# Flight-Mill-Controller.net
KiCad netlist of a schematic drawn in EAGLE
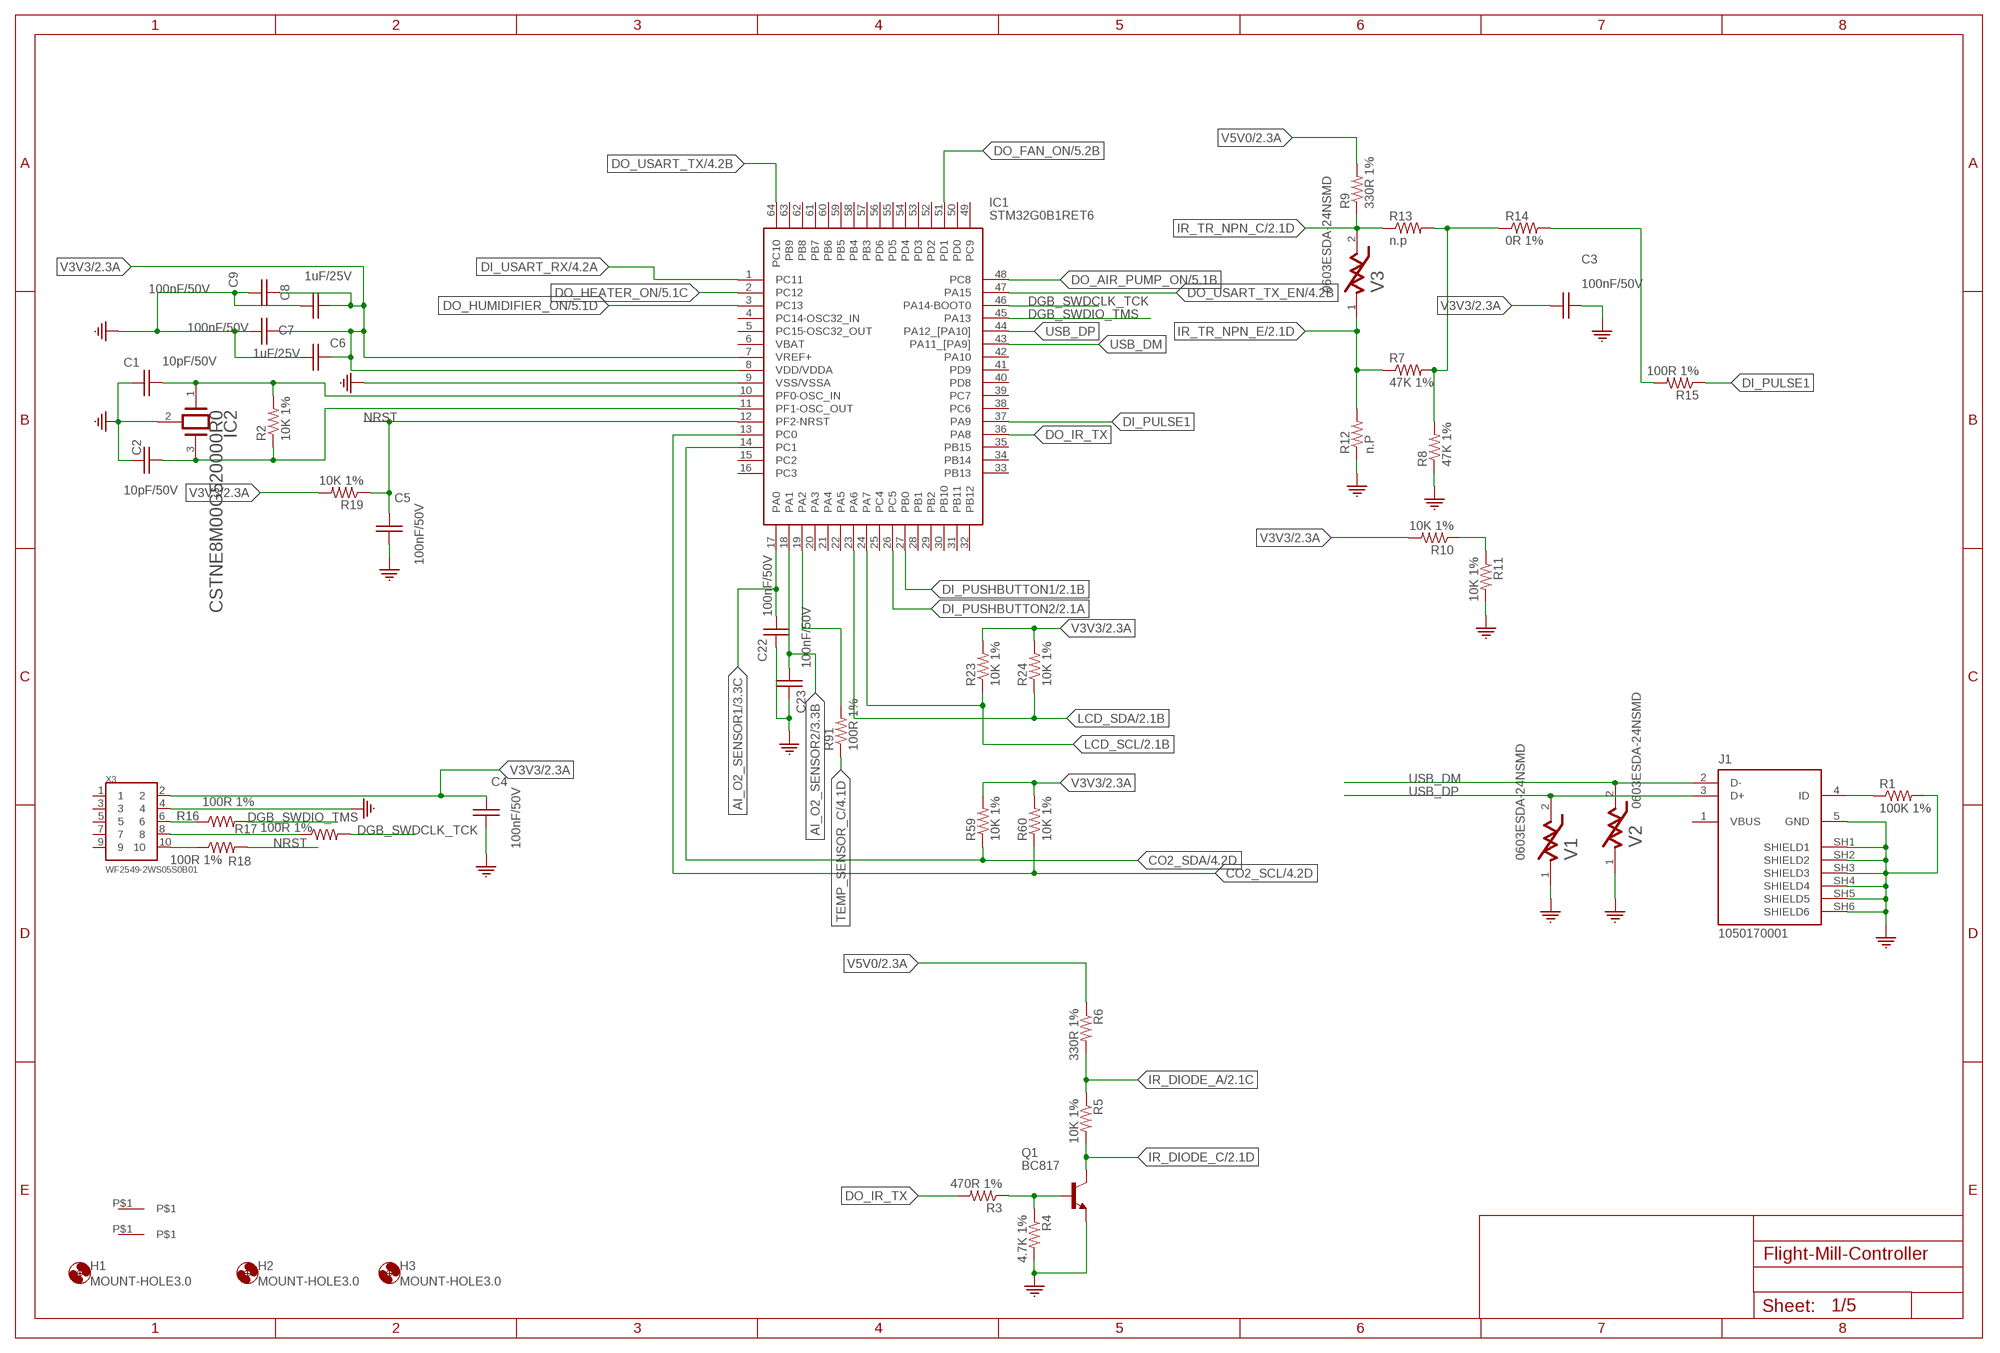
[diagram p0: schematic, sheet 1]
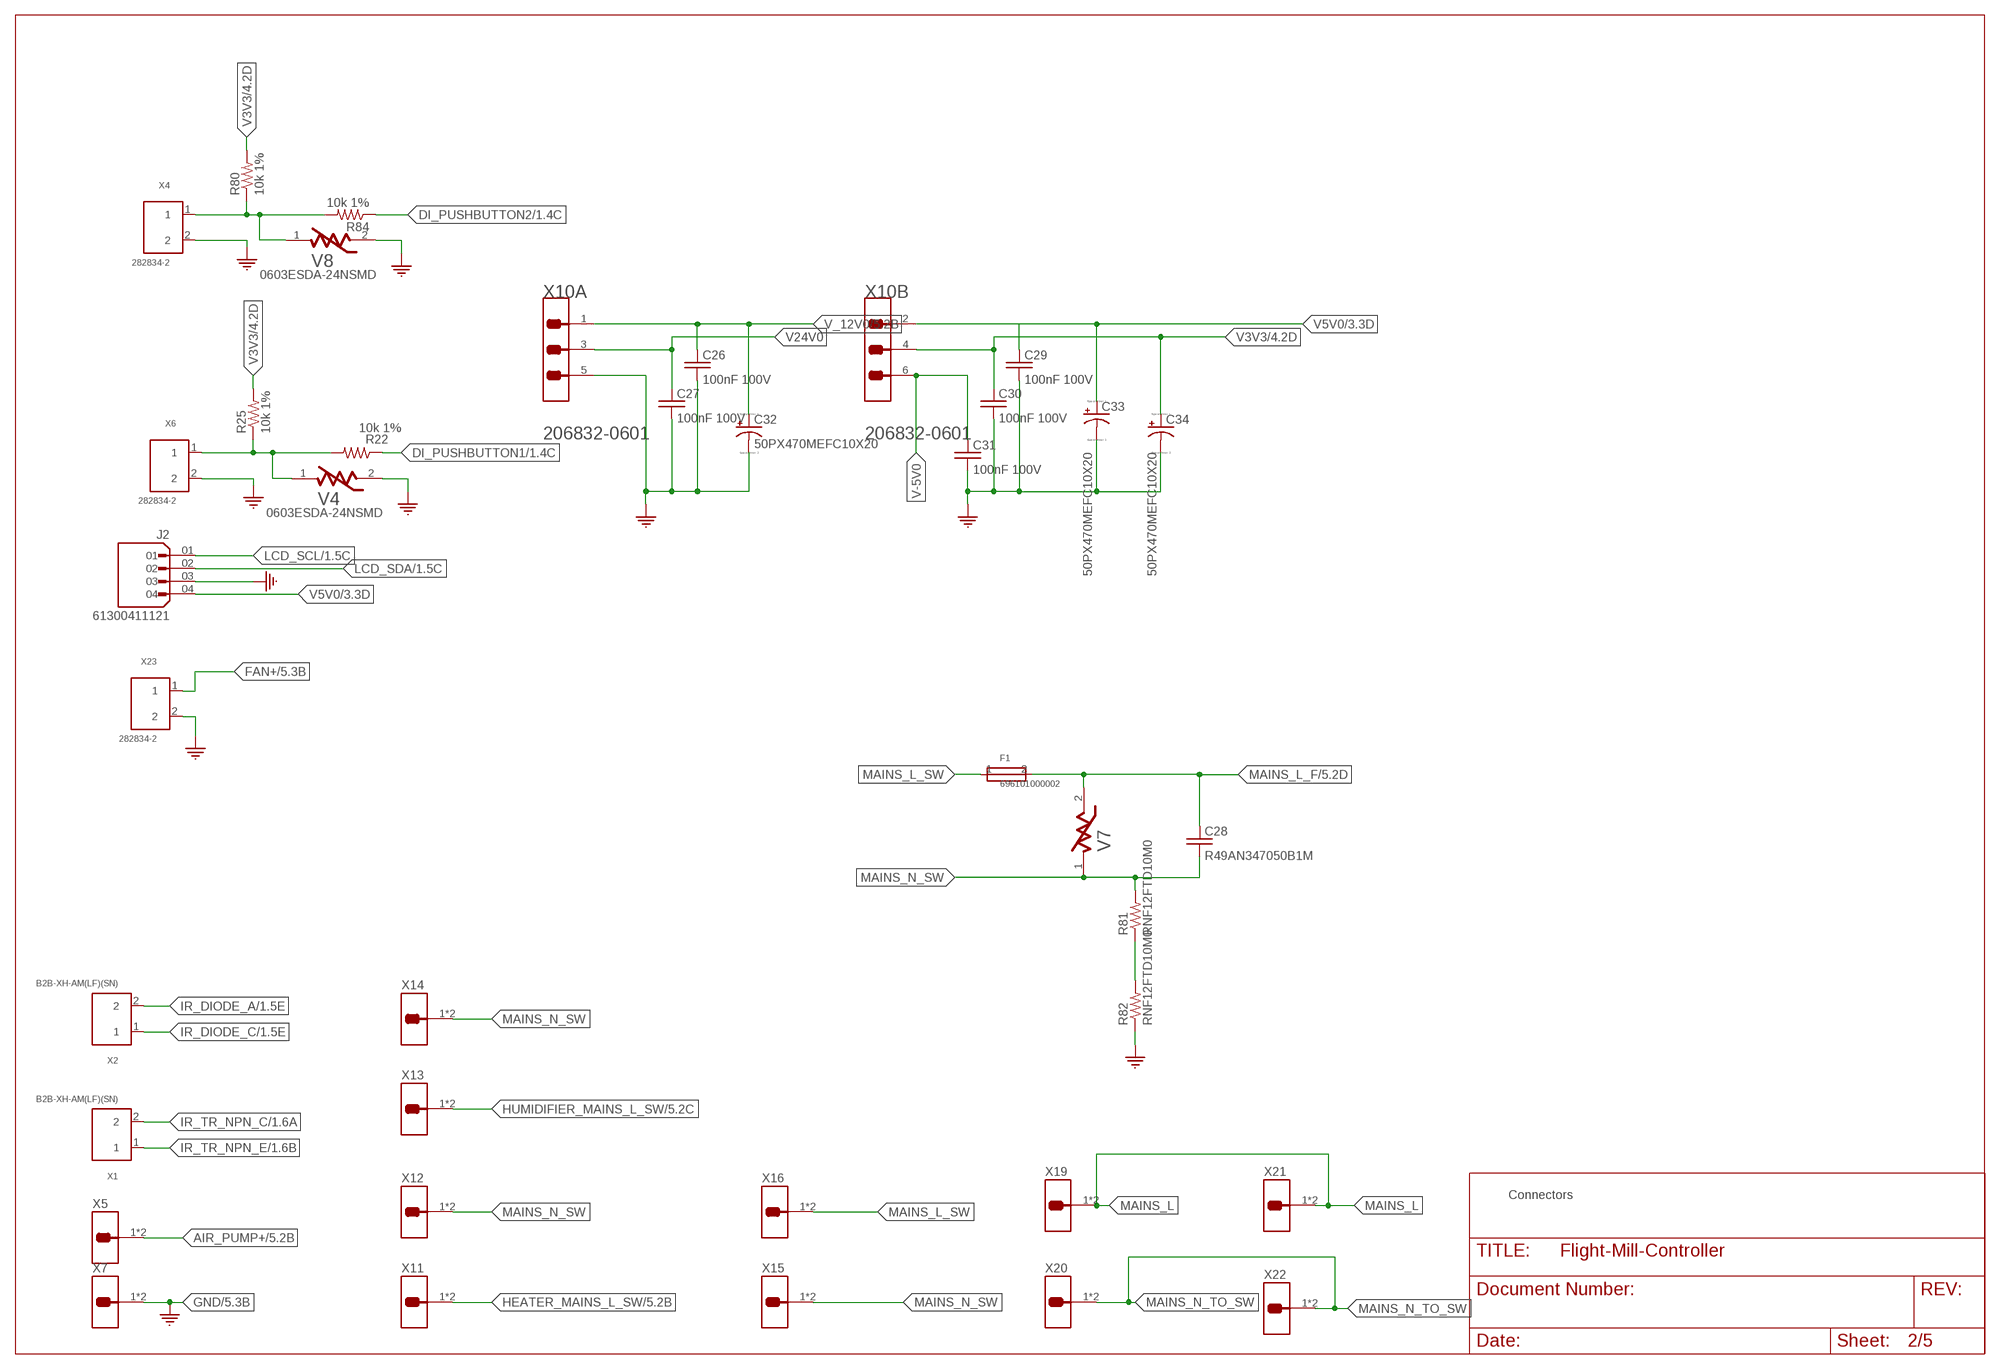
[diagram p1: schematic, sheet 2]
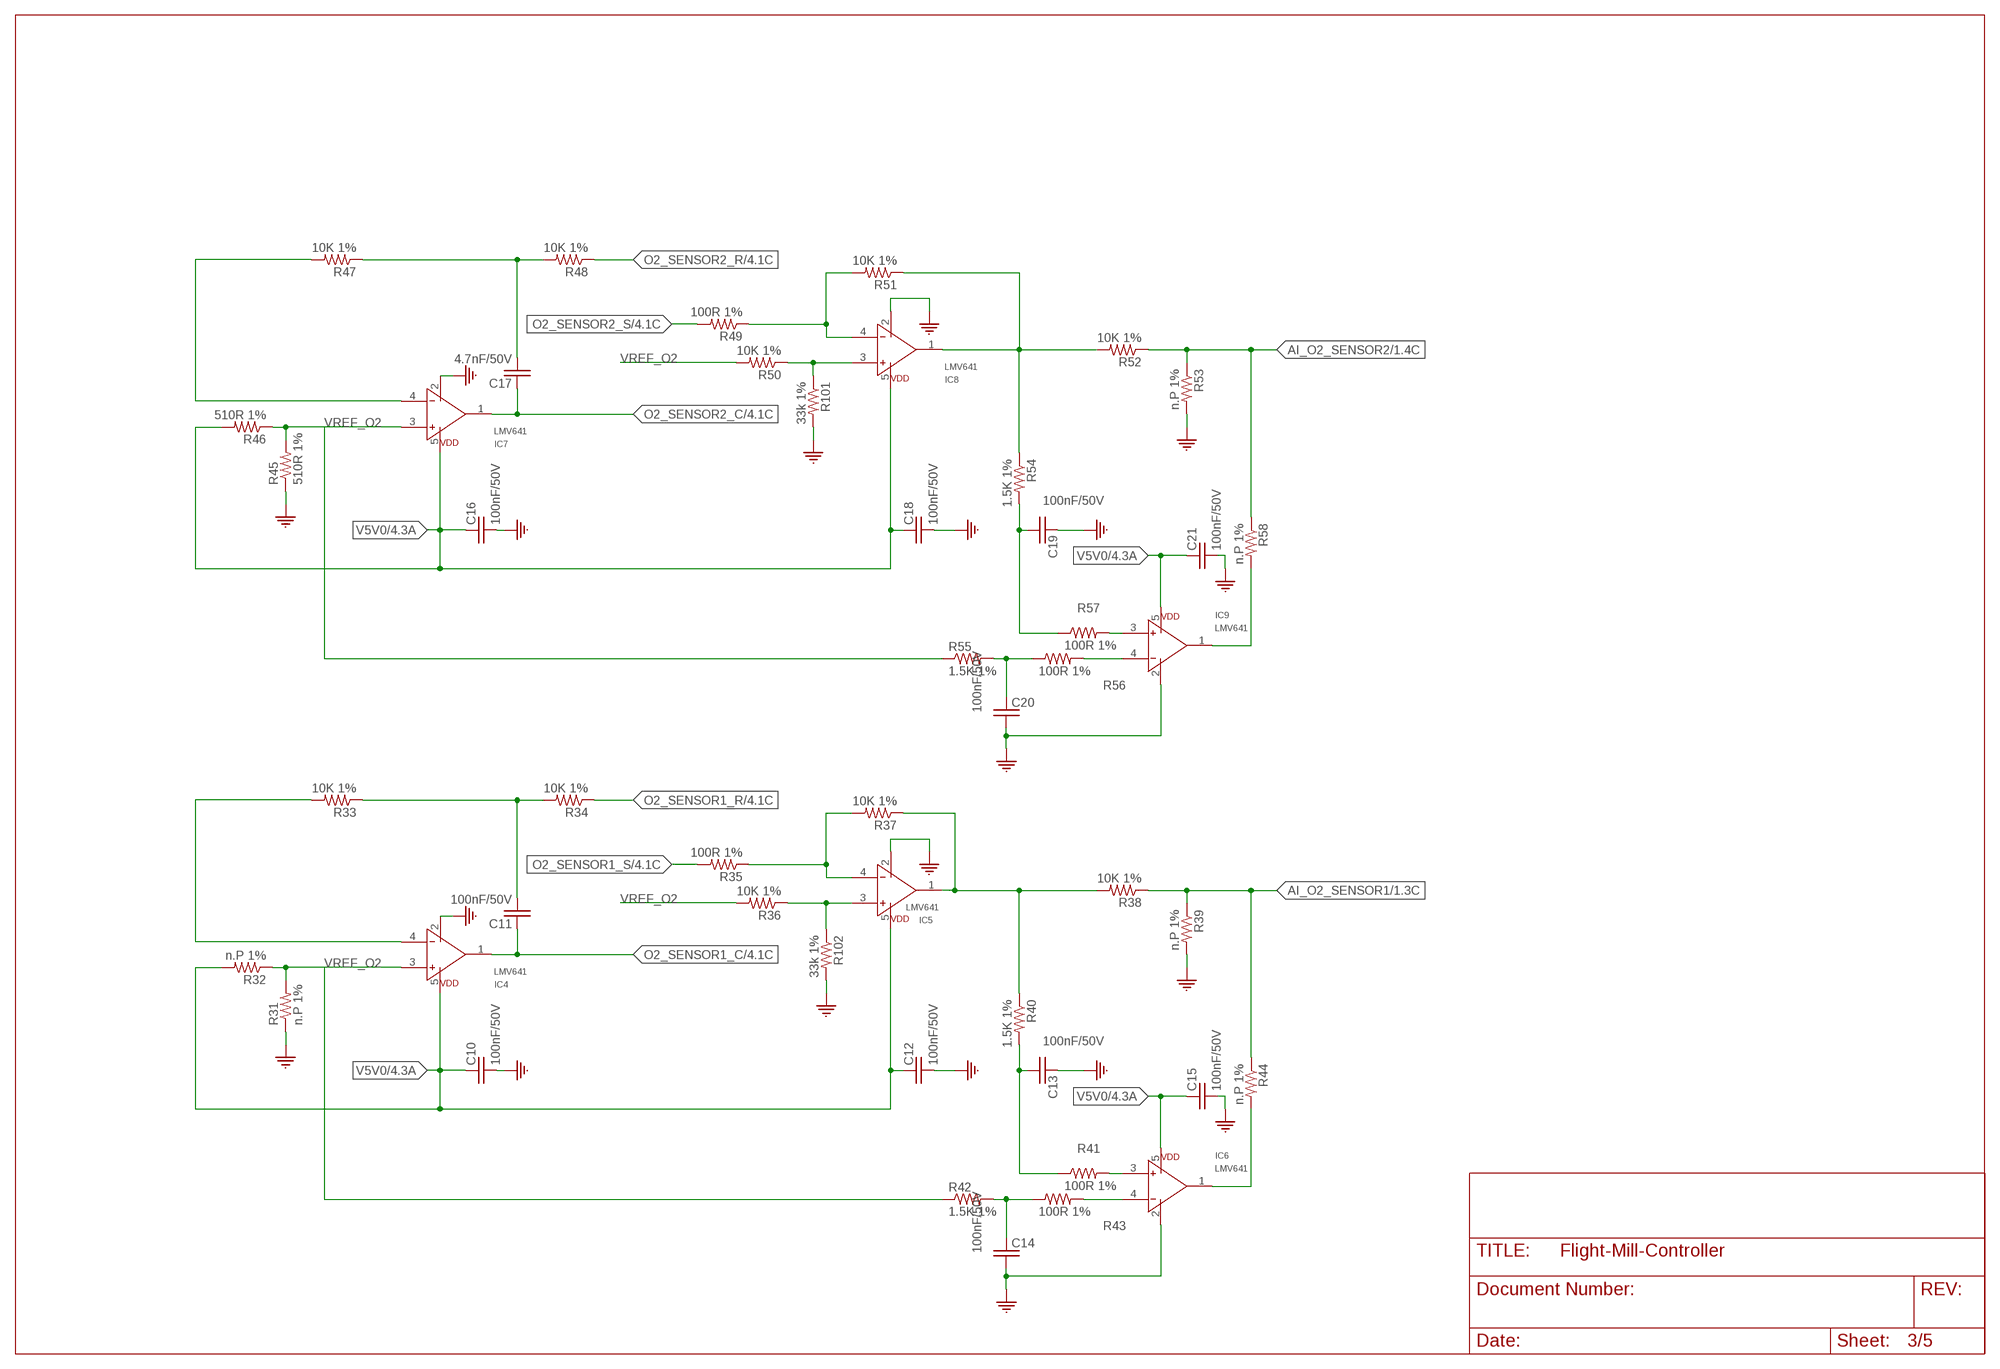
[diagram p2: schematic, sheet 3]
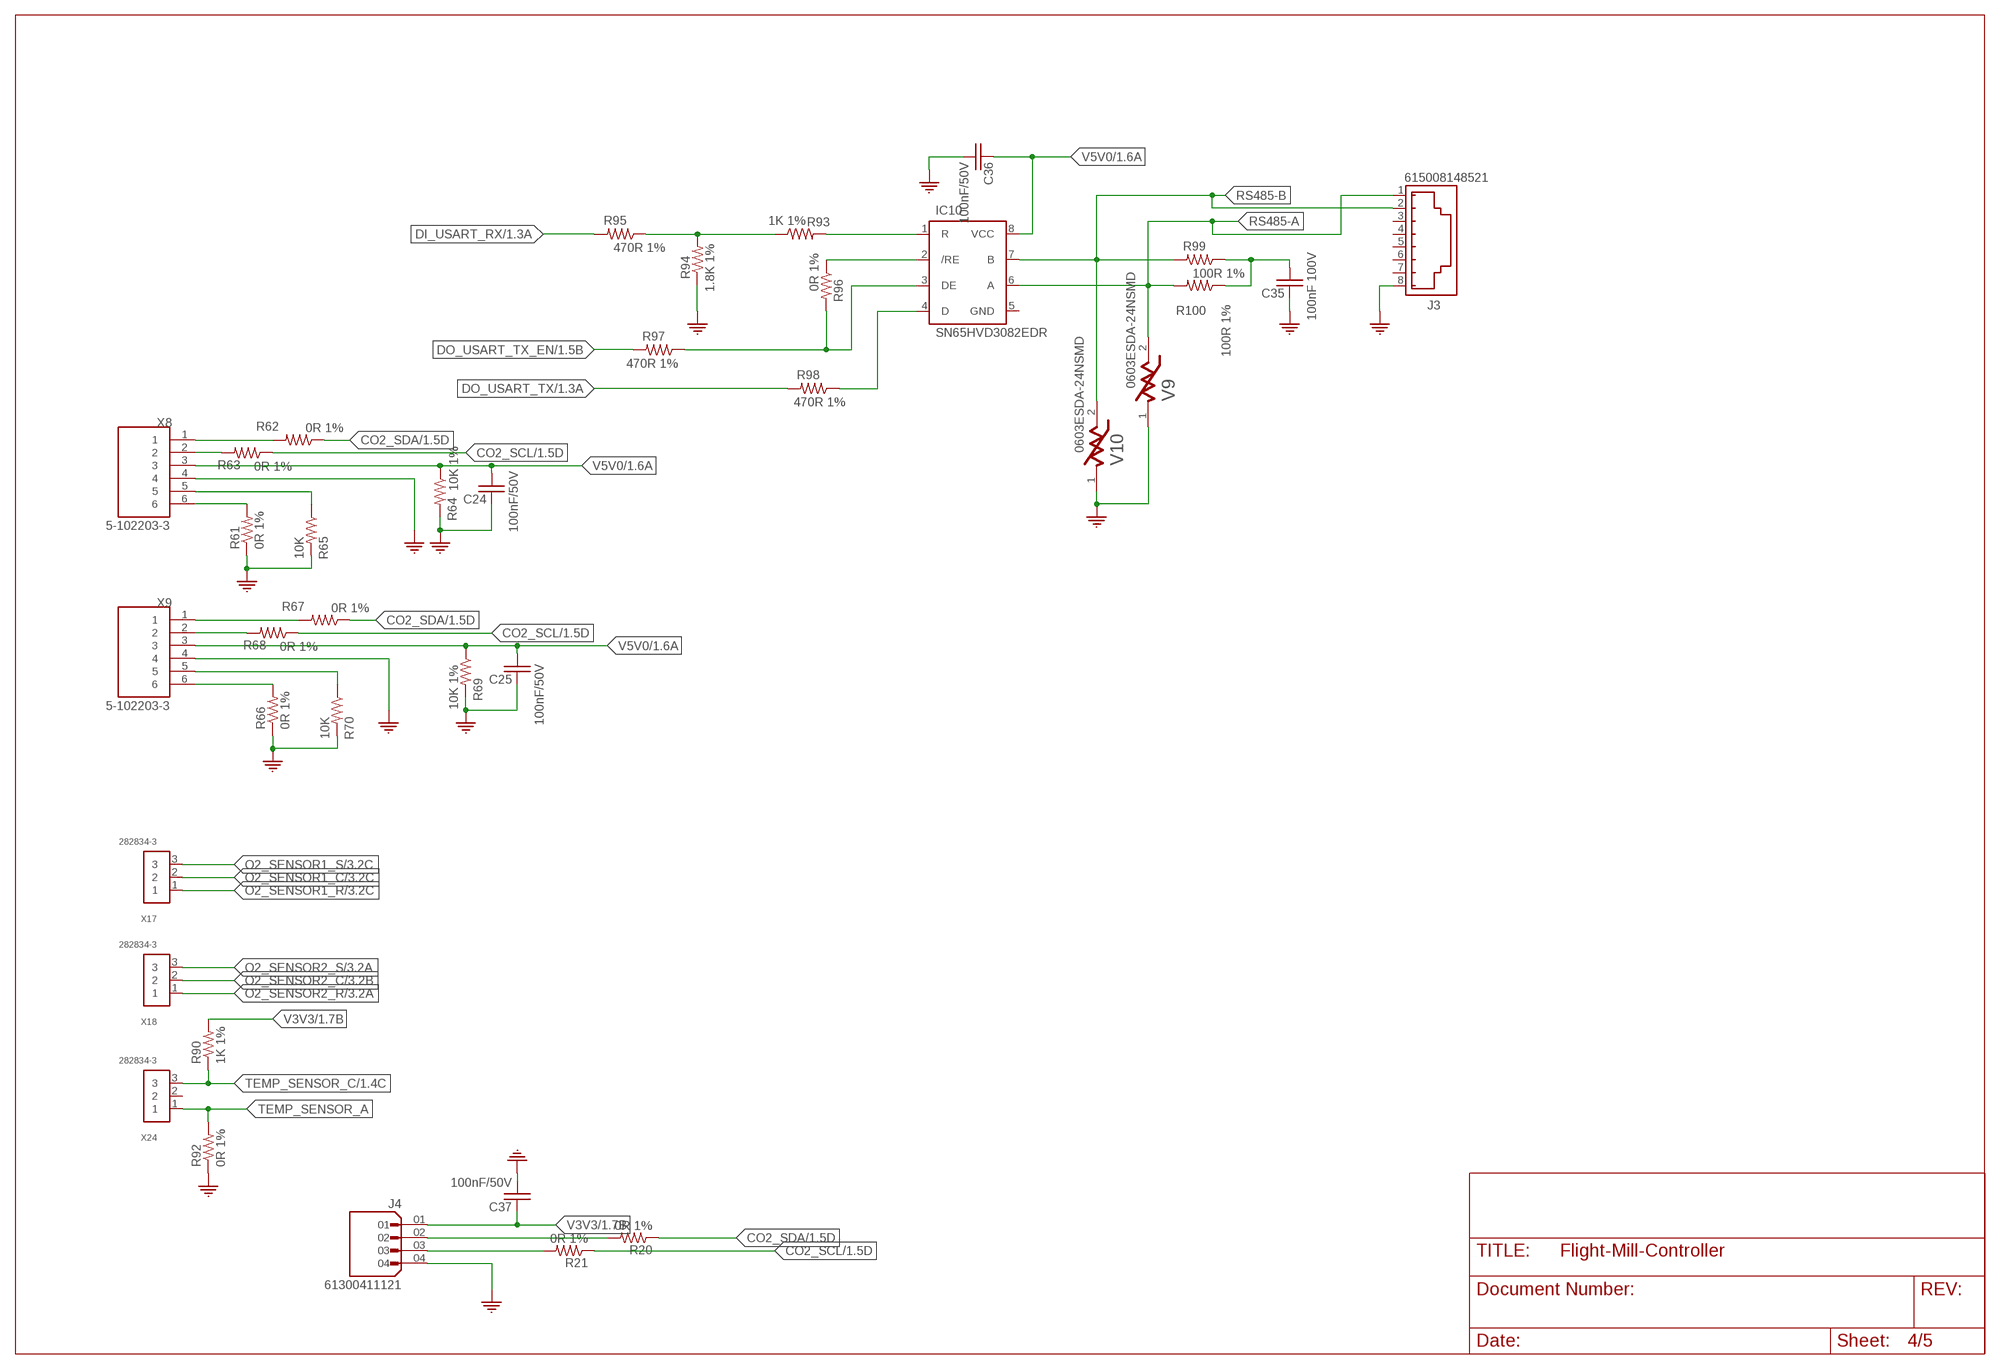
[diagram p3: schematic, sheet 4]
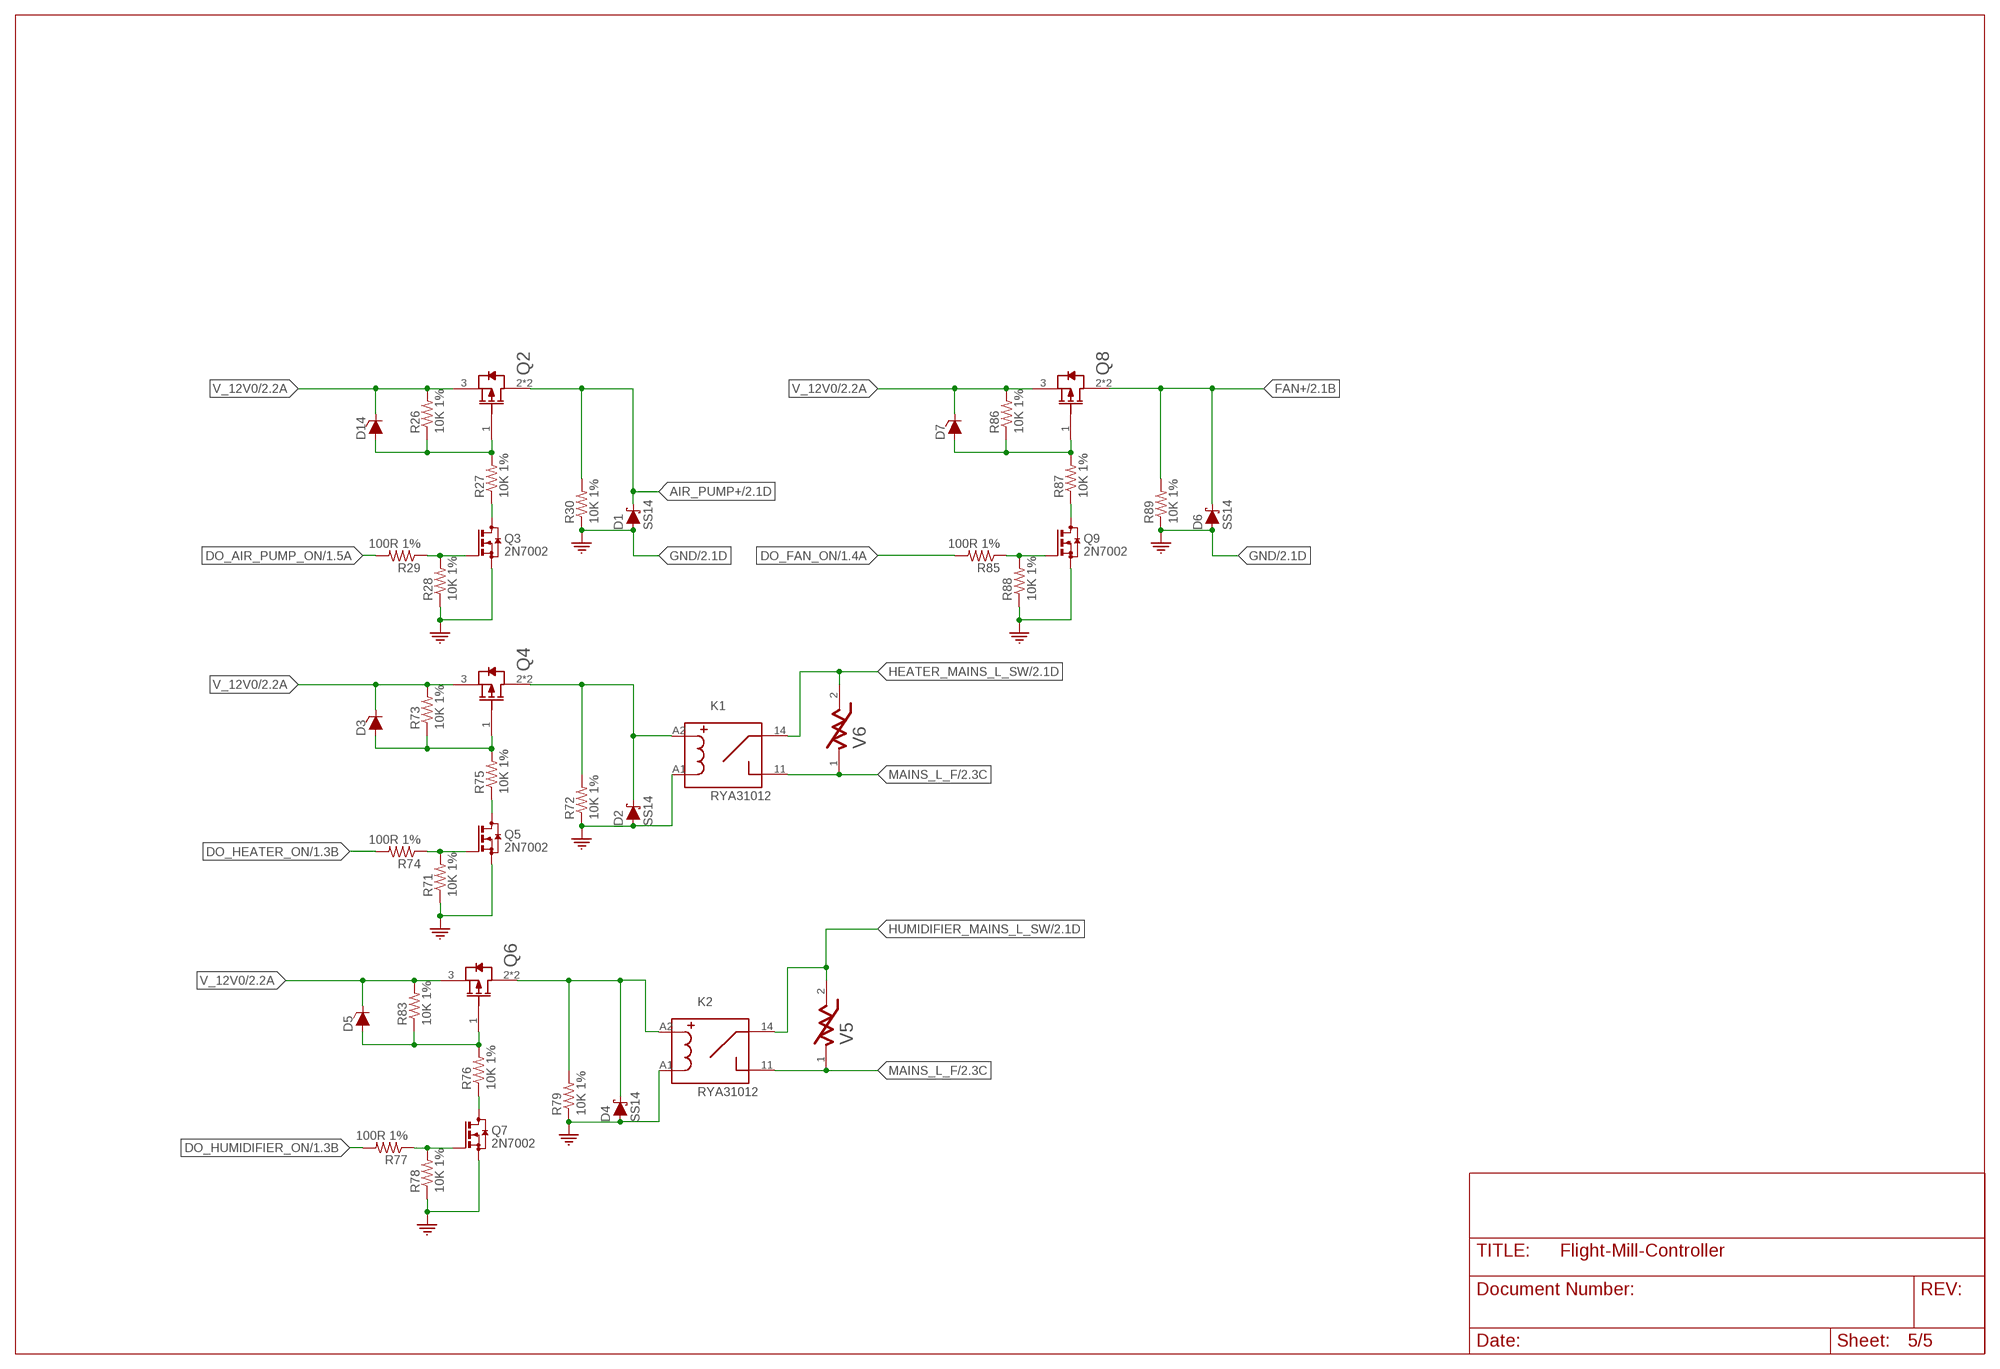
[diagram p4: schematic, sheet 5]

(export (version "E")
  (design (tool "Eeschema 10.0.6"))
  (components
    (comp (ref "C1")
      (value "10pF/50V")
      (footprint "eagle-import:EIA0603")
      (libsource (lib "eagle-import") (part "C_0603EIA0603"))
    )
    (comp (ref "C2")
      (value "10pF/50V")
      (footprint "eagle-import:EIA0603")
      (libsource (lib "eagle-import") (part "C_0603EIA0603"))
    )
    (comp (ref "C3")
      (value "100nF/50V")
      (footprint "eagle-import:EIA0603")
      (libsource (lib "eagle-import") (part "C_0603EIA0603"))
    )
    (comp (ref "C4")
      (value "100nF/50V")
      (footprint "eagle-import:EIA0603")
      (libsource (lib "eagle-import") (part "C_0603EIA0603"))
    )
    (comp (ref "C5")
      (value "100nF/50V")
      (footprint "eagle-import:EIA0603")
      (libsource (lib "eagle-import") (part "C_0603EIA0603"))
    )
    (comp (ref "C6")
      (value "1uF/25V")
      (footprint "eagle-import:EIA0603")
      (libsource (lib "eagle-import") (part "C_0603EIA0603"))
    )
    (comp (ref "C7")
      (value "100nF/50V")
      (footprint "eagle-import:EIA0603")
      (libsource (lib "eagle-import") (part "C_0603EIA0603"))
    )
    (comp (ref "C8")
      (value "1uF/25V")
      (footprint "eagle-import:EIA0603")
      (libsource (lib "eagle-import") (part "C_0603EIA0603"))
    )
    (comp (ref "C9")
      (value "100nF/50V")
      (footprint "eagle-import:EIA0603")
      (libsource (lib "eagle-import") (part "C_0603EIA0603"))
    )
    (comp (ref "C22")
      (value "100nF/50V")
      (footprint "eagle-import:EIA0603")
      (libsource (lib "eagle-import") (part "C_0603EIA0603"))
    )
    (comp (ref "C23")
      (value "100nF/50V")
      (footprint "eagle-import:EIA0603")
      (libsource (lib "eagle-import") (part "C_0603EIA0603"))
    )
    (comp (ref "FID1")
      (value "FIDUCIAL")
      (footprint "eagle-import:FIDUCIAL")
      (libsource (lib "eagle-import") (part "FIDUCIAL"))
    )
    (comp (ref "FID2")
      (value "FIDUCIAL")
      (footprint "eagle-import:FIDUCIAL")
      (libsource (lib "eagle-import") (part "FIDUCIAL"))
    )
    (comp (ref "H1")
      (value "MOUNT-HOLE3.0")
      (footprint "eagle-import:3,0")
      (libsource (lib "eagle-import") (part "MOUNT-HOLE3.0"))
    )
    (comp (ref "H2")
      (value "MOUNT-HOLE3.0")
      (footprint "eagle-import:3,0")
      (libsource (lib "eagle-import") (part "MOUNT-HOLE3.0"))
    )
    (comp (ref "H3")
      (value "MOUNT-HOLE3.0")
      (footprint "eagle-import:3,0")
      (libsource (lib "eagle-import") (part "MOUNT-HOLE3.0"))
    )
    (comp (ref "IC1")
      (value "STM32G0B1RET6")
      (footprint "eagle-import:QFP50P1200X1200X160-64N")
      (fields (field (name "MOUSER_PART_NUMBER") "511-STM32G0B1RET6"))
      (libsource (lib "eagle-import") (part "STM32G0B1RET6"))
    )
    (comp (ref "IC2")
      (value "CSTNE8M00G520000R0")
      (footprint "eagle-import:CSTNE8M00G520000R0")
      (fields (field (name "MFR") "Murata"))
      (libsource (lib "eagle-import") (part "CSTNE8M00G520000R0"))
    )
    (comp (ref "J1")
      (value "1050170001")
      (footprint "eagle-import:MOLEX_1050170001")
      (fields (field (name "MF") "Molex"))
      (libsource (lib "eagle-import") (part "1050170001"))
    )
    (comp (ref "Q1")
      (value "BC817")
      (footprint "eagle-import:SOT23")
      (fields (field (name "MFR") "NXP"))
      (libsource (lib "eagle-import") (part "BC817"))
    )
    (comp (ref "R1")
      (value "100K 1%")
      (footprint "eagle-import:EIA0603")
      (libsource (lib "eagle-import") (part "R_0603"))
    )
    (comp (ref "R2")
      (value "10K 1%")
      (footprint "eagle-import:EIA0603")
      (libsource (lib "eagle-import") (part "R_0603"))
    )
    (comp (ref "R3")
      (value "470R 1%")
      (footprint "eagle-import:EIA0603")
      (libsource (lib "eagle-import") (part "R_0603"))
    )
    (comp (ref "R4")
      (value "4.7K 1%")
      (footprint "eagle-import:EIA0603")
      (libsource (lib "eagle-import") (part "R_0603"))
    )
    (comp (ref "R5")
      (value "10K 1%")
      (footprint "eagle-import:EIA0603")
      (libsource (lib "eagle-import") (part "R_0603"))
    )
    (comp (ref "R6")
      (value "330R 1%")
      (footprint "eagle-import:EIA0603")
      (libsource (lib "eagle-import") (part "R_0603"))
    )
    (comp (ref "R7")
      (value "47K 1%")
      (footprint "eagle-import:EIA0603")
      (libsource (lib "eagle-import") (part "R_0603"))
    )
    (comp (ref "R8")
      (value "47K 1%")
      (footprint "eagle-import:EIA0603")
      (libsource (lib "eagle-import") (part "R_0603"))
    )
    (comp (ref "R9")
      (value "330R 1%")
      (footprint "eagle-import:EIA0603")
      (libsource (lib "eagle-import") (part "R_0603"))
    )
    (comp (ref "R10")
      (value "10K 1%")
      (footprint "eagle-import:EIA0603")
      (libsource (lib "eagle-import") (part "R_0603"))
    )
    (comp (ref "R11")
      (value "10K 1%")
      (footprint "eagle-import:EIA0603")
      (libsource (lib "eagle-import") (part "R_0603"))
    )
    (comp (ref "R12")
      (value "n.P")
      (footprint "eagle-import:EIA0603")
      (libsource (lib "eagle-import") (part "R_0603"))
    )
    (comp (ref "R13")
      (value "n.p")
      (footprint "eagle-import:EIA0603")
      (libsource (lib "eagle-import") (part "R_0603"))
    )
    (comp (ref "R14")
      (value "0R 1%")
      (footprint "eagle-import:EIA0603")
      (libsource (lib "eagle-import") (part "R_0603"))
    )
    (comp (ref "R15")
      (value "100R 1%")
      (footprint "eagle-import:EIA0603")
      (libsource (lib "eagle-import") (part "R_0603"))
    )
    (comp (ref "R16")
      (value "100R 1%")
      (footprint "eagle-import:EIA0603")
      (libsource (lib "eagle-import") (part "R_0603"))
    )
    (comp (ref "R17")
      (value "100R 1%")
      (footprint "eagle-import:EIA0603")
      (libsource (lib "eagle-import") (part "R_0603"))
    )
    (comp (ref "R18")
      (value "100R 1%")
      (footprint "eagle-import:EIA0603")
      (libsource (lib "eagle-import") (part "R_0603"))
    )
    (comp (ref "R19")
      (value "10K 1%")
      (footprint "eagle-import:EIA0603")
      (libsource (lib "eagle-import") (part "R_0603"))
    )
    (comp (ref "R23")
      (value "10K 1%")
      (footprint "eagle-import:EIA0603")
      (libsource (lib "eagle-import") (part "R_0603"))
    )
    (comp (ref "R24")
      (value "10K 1%")
      (footprint "eagle-import:EIA0603")
      (libsource (lib "eagle-import") (part "R_0603"))
    )
    (comp (ref "R59")
      (value "10K 1%")
      (footprint "eagle-import:EIA0603")
      (libsource (lib "eagle-import") (part "R_0603"))
    )
    (comp (ref "R60")
      (value "10K 1%")
      (footprint "eagle-import:EIA0603")
      (libsource (lib "eagle-import") (part "R_0603"))
    )
    (comp (ref "R91")
      (value "100R 1%")
      (footprint "eagle-import:EIA0603")
      (libsource (lib "eagle-import") (part "R_0603"))
    )
    (comp (ref "V1")
      (value "0603ESDA-24NSMD")
      (footprint "eagle-import:EIA0603")
      (fields (field (name "MFR") "Bourns"))
      (libsource (lib "eagle-import") (part "0603ESDA-24NSMD"))
    )
    (comp (ref "V2")
      (value "0603ESDA-24NSMD")
      (footprint "eagle-import:EIA0603")
      (fields (field (name "MFR") "Bourns"))
      (libsource (lib "eagle-import") (part "0603ESDA-24NSMD"))
    )
    (comp (ref "V3")
      (value "0603ESDA-24NSMD")
      (footprint "eagle-import:EIA0603")
      (fields (field (name "MFR") "Bourns"))
      (libsource (lib "eagle-import") (part "0603ESDA-24NSMD"))
    )
    (comp (ref "X3")
      (value "WF2549-2WS05S0B01")
      (footprint "eagle-import:X10_100MIL_2XROW_VERT")
      (fields (field (name "MFR") "WCON"))
      (libsource (lib "eagle-import") (part "WF2549-2WS05S0B01"))
    )
    (comp (ref "C24")
      (value "100nF/50V")
      (footprint "eagle-import:EIA0603")
      (libsource (lib "eagle-import") (part "C_0603EIA0603"))
    )
    (comp (ref "C25")
      (value "100nF/50V")
      (footprint "eagle-import:EIA0603")
      (libsource (lib "eagle-import") (part "C_0603EIA0603"))
    )
    (comp (ref "C35")
      (value "100nF 100V")
      (footprint "eagle-import:EIA0603")
      (libsource (lib "eagle-import") (part "C_0603EIA0603"))
    )
    (comp (ref "C36")
      (value "100nF/50V")
      (footprint "eagle-import:EIA0603")
      (libsource (lib "eagle-import") (part "C_0603EIA0603"))
    )
    (comp (ref "C37")
      (value "100nF/50V")
      (footprint "eagle-import:EIA0603")
      (libsource (lib "eagle-import") (part "C_0603EIA0603"))
    )
    (comp (ref "IC10")
      (value "SN65HVD3082EDR")
      (footprint "eagle-import:SOIC8")
      (fields (field (name "MFR") "TI,3Peak"))
      (libsource (lib "eagle-import") (part "SN65HVD3082EDR"))
    )
    (comp (ref "J3")
      (value "615008148521")
      (footprint "eagle-import:615008148521")
      (fields (field (name "MFR") "Wurth Elektronik"))
      (libsource (lib "eagle-import") (part "615008148521"))
    )
    (comp (ref "J4")
      (value "61300411121")
      (footprint "eagle-import:X04_100MIL_1ROW")
      (fields (field (name "MFR") "Wurth Electronics"))
      (libsource (lib "eagle-import") (part "61300411121"))
    )
    (comp (ref "R20")
      (value "0R 1%")
      (footprint "eagle-import:EIA0603")
      (libsource (lib "eagle-import") (part "R_0603"))
    )
    (comp (ref "R21")
      (value "0R 1%")
      (footprint "eagle-import:EIA0603")
      (libsource (lib "eagle-import") (part "R_0603"))
    )
    (comp (ref "R61")
      (value "0R 1%")
      (footprint "eagle-import:EIA0603")
      (libsource (lib "eagle-import") (part "R_0603"))
    )
    (comp (ref "R62")
      (value "0R 1%")
      (footprint "eagle-import:EIA0603")
      (libsource (lib "eagle-import") (part "R_0603"))
    )
    (comp (ref "R63")
      (value "0R 1%")
      (footprint "eagle-import:EIA0603")
      (libsource (lib "eagle-import") (part "R_0603"))
    )
    (comp (ref "R64")
      (value "10K 1%")
      (footprint "eagle-import:EIA0603")
      (libsource (lib "eagle-import") (part "R_0603"))
    )
    (comp (ref "R65")
      (value "10K")
      (footprint "eagle-import:EIA0603")
      (libsource (lib "eagle-import") (part "R_0603"))
    )
    (comp (ref "R66")
      (value "0R 1%")
      (footprint "eagle-import:EIA0603")
      (libsource (lib "eagle-import") (part "R_0603"))
    )
    (comp (ref "R67")
      (value "0R 1%")
      (footprint "eagle-import:EIA0603")
      (libsource (lib "eagle-import") (part "R_0603"))
    )
    (comp (ref "R68")
      (value "0R 1%")
      (footprint "eagle-import:EIA0603")
      (libsource (lib "eagle-import") (part "R_0603"))
    )
    (comp (ref "R69")
      (value "10K 1%")
      (footprint "eagle-import:EIA0603")
      (libsource (lib "eagle-import") (part "R_0603"))
    )
    (comp (ref "R70")
      (value "10K")
      (footprint "eagle-import:EIA0603")
      (libsource (lib "eagle-import") (part "R_0603"))
    )
    (comp (ref "R90")
      (value "1K 1%")
      (footprint "eagle-import:EIA0603")
      (libsource (lib "eagle-import") (part "R_0603"))
    )
    (comp (ref "R92")
      (value "0R 1%")
      (footprint "eagle-import:EIA0603")
      (libsource (lib "eagle-import") (part "R_0603"))
    )
    (comp (ref "R93")
      (value "1K 1%")
      (footprint "eagle-import:EIA0603")
      (libsource (lib "eagle-import") (part "R_0603"))
    )
    (comp (ref "R94")
      (value "1.8K 1%")
      (footprint "eagle-import:EIA0603")
      (libsource (lib "eagle-import") (part "R_0603"))
    )
    (comp (ref "R95")
      (value "470R 1%")
      (footprint "eagle-import:EIA0603")
      (libsource (lib "eagle-import") (part "R_0603"))
    )
    (comp (ref "R96")
      (value "0R 1%")
      (footprint "eagle-import:EIA0603")
      (libsource (lib "eagle-import") (part "R_0603"))
    )
    (comp (ref "R97")
      (value "470R 1%")
      (footprint "eagle-import:EIA0603")
      (libsource (lib "eagle-import") (part "R_0603"))
    )
    (comp (ref "R98")
      (value "470R 1%")
      (footprint "eagle-import:EIA0603")
      (libsource (lib "eagle-import") (part "R_0603"))
    )
    (comp (ref "R99")
      (value "100R 1%")
      (footprint "eagle-import:EIA0603")
      (libsource (lib "eagle-import") (part "R_0603"))
    )
    (comp (ref "R100")
      (value "100R 1%")
      (footprint "eagle-import:EIA0603")
      (libsource (lib "eagle-import") (part "R_0603"))
    )
    (comp (ref "V9")
      (value "0603ESDA-24NSMD")
      (footprint "eagle-import:EIA0603")
      (fields (field (name "MFR") "Bourns"))
      (libsource (lib "eagle-import") (part "0603ESDA-24NSMD"))
    )
    (comp (ref "V10")
      (value "0603ESDA-24NSMD")
      (footprint "eagle-import:EIA0603")
      (fields (field (name "MFR") "Bourns"))
      (libsource (lib "eagle-import") (part "0603ESDA-24NSMD"))
    )
    (comp (ref "X8")
      (value "5-102203-3")
      (footprint "eagle-import:TE_5-102203-3")
      (fields (field (name "MFR") "TE Connectivity"))
      (libsource (lib "eagle-import") (part "5-102203-3"))
    )
    (comp (ref "X9")
      (value "5-102203-3")
      (footprint "eagle-import:TE_5-102203-3")
      (fields (field (name "MFR") "TE Connectivity"))
      (libsource (lib "eagle-import") (part "5-102203-3"))
    )
    (comp (ref "X17")
      (value "282834-3")
      (footprint "eagle-import:TE_282834-3_0")
      (fields (field (name "MFR") "TE"))
      (libsource (lib "eagle-import") (part "282834-3"))
    )
    (comp (ref "X18")
      (value "282834-3")
      (footprint "eagle-import:TE_282834-3_0")
      (fields (field (name "MFR") "TE"))
      (libsource (lib "eagle-import") (part "282834-3"))
    )
    (comp (ref "X24")
      (value "282834-3")
      (footprint "eagle-import:TE_282834-3_0")
      (fields (field (name "MFR") "TE"))
      (libsource (lib "eagle-import") (part "282834-3"))
    )
    (comp (ref "C10")
      (value "100nF/50V")
      (footprint "eagle-import:EIA0603")
      (libsource (lib "eagle-import") (part "C_0603EIA0603"))
    )
    (comp (ref "C11")
      (value "100nF/50V")
      (footprint "eagle-import:EIA0603")
      (libsource (lib "eagle-import") (part "C_0603EIA0603"))
    )
    (comp (ref "C12")
      (value "100nF/50V")
      (footprint "eagle-import:EIA0603")
      (libsource (lib "eagle-import") (part "C_0603EIA0603"))
    )
    (comp (ref "C13")
      (value "100nF/50V")
      (footprint "eagle-import:EIA0603")
      (libsource (lib "eagle-import") (part "C_0603EIA0603"))
    )
    (comp (ref "C14")
      (value "100nF/50V")
      (footprint "eagle-import:EIA0603")
      (libsource (lib "eagle-import") (part "C_0603EIA0603"))
    )
    (comp (ref "C15")
      (value "100nF/50V")
      (footprint "eagle-import:EIA0603")
      (libsource (lib "eagle-import") (part "C_0603EIA0603"))
    )
    (comp (ref "C16")
      (value "100nF/50V")
      (footprint "eagle-import:EIA0603")
      (libsource (lib "eagle-import") (part "C_0603EIA0603"))
    )
    (comp (ref "C17")
      (value "4.7nF/50V")
      (footprint "eagle-import:EIA0603")
      (libsource (lib "eagle-import") (part "C_0603EIA0603"))
    )
    (comp (ref "C18")
      (value "100nF/50V")
      (footprint "eagle-import:EIA0603")
      (libsource (lib "eagle-import") (part "C_0603EIA0603"))
    )
    (comp (ref "C19")
      (value "100nF/50V")
      (footprint "eagle-import:EIA0603")
      (libsource (lib "eagle-import") (part "C_0603EIA0603"))
    )
    (comp (ref "C20")
      (value "100nF/50V")
      (footprint "eagle-import:EIA0603")
      (libsource (lib "eagle-import") (part "C_0603EIA0603"))
    )
    (comp (ref "C21")
      (value "100nF/50V")
      (footprint "eagle-import:EIA0603")
      (libsource (lib "eagle-import") (part "C_0603EIA0603"))
    )
    (comp (ref "IC4")
      (value "LMV641")
      (footprint "eagle-import:SOT-23-5")
      (fields (field (name "MFR") "Texas Instruments"))
      (libsource (lib "eagle-import") (part "LMV641"))
    )
    (comp (ref "IC5")
      (value "LMV641")
      (footprint "eagle-import:SOT-23-5")
      (fields (field (name "MFR") "Texas Instruments"))
      (libsource (lib "eagle-import") (part "LMV641"))
    )
    (comp (ref "IC6")
      (value "LMV641")
      (footprint "eagle-import:SOT-23-5")
      (fields (field (name "MFR") "Texas Instruments"))
      (libsource (lib "eagle-import") (part "LMV641"))
    )
    (comp (ref "IC7")
      (value "LMV641")
      (footprint "eagle-import:SOT-23-5")
      (fields (field (name "MFR") "Texas Instruments"))
      (libsource (lib "eagle-import") (part "LMV641"))
    )
    (comp (ref "IC8")
      (value "LMV641")
      (footprint "eagle-import:SOT-23-5")
      (fields (field (name "MFR") "Texas Instruments"))
      (libsource (lib "eagle-import") (part "LMV641"))
    )
    (comp (ref "IC9")
      (value "LMV641")
      (footprint "eagle-import:SOT-23-5")
      (fields (field (name "MFR") "Texas Instruments"))
      (libsource (lib "eagle-import") (part "LMV641"))
    )
    (comp (ref "R31")
      (value "n.P 1%")
      (footprint "eagle-import:EIA0603")
      (libsource (lib "eagle-import") (part "R_0603"))
    )
    (comp (ref "R32")
      (value "n.P 1%")
      (footprint "eagle-import:EIA0603")
      (libsource (lib "eagle-import") (part "R_0603"))
    )
    (comp (ref "R33")
      (value "10K 1%")
      (footprint "eagle-import:EIA0603")
      (libsource (lib "eagle-import") (part "R_0603"))
    )
    (comp (ref "R34")
      (value "10K 1%")
      (footprint "eagle-import:EIA0603")
      (libsource (lib "eagle-import") (part "R_0603"))
    )
    (comp (ref "R35")
      (value "100R 1%")
      (footprint "eagle-import:EIA0603")
      (libsource (lib "eagle-import") (part "R_0603"))
    )
    (comp (ref "R36")
      (value "10K 1%")
      (footprint "eagle-import:EIA0603")
      (libsource (lib "eagle-import") (part "R_0603"))
    )
    (comp (ref "R37")
      (value "10K 1%")
      (footprint "eagle-import:EIA0603")
      (libsource (lib "eagle-import") (part "R_0603"))
    )
    (comp (ref "R38")
      (value "10K 1%")
      (footprint "eagle-import:EIA0603")
      (libsource (lib "eagle-import") (part "R_0603"))
    )
    (comp (ref "R39")
      (value "n.P 1%")
      (footprint "eagle-import:EIA0603")
      (libsource (lib "eagle-import") (part "R_0603"))
    )
    (comp (ref "R40")
      (value "1.5K 1%")
      (footprint "eagle-import:EIA0603")
      (libsource (lib "eagle-import") (part "R_0603"))
    )
    (comp (ref "R41")
      (value "100R 1%")
      (footprint "eagle-import:EIA0603")
      (libsource (lib "eagle-import") (part "R_0603"))
    )
    (comp (ref "R42")
      (value "1.5K 1%")
      (footprint "eagle-import:EIA0603")
      (libsource (lib "eagle-import") (part "R_0603"))
    )
    (comp (ref "R43")
      (value "100R 1%")
      (footprint "eagle-import:EIA0603")
      (libsource (lib "eagle-import") (part "R_0603"))
    )
    (comp (ref "R44")
      (value "n.P 1%")
      (footprint "eagle-import:EIA0603")
      (libsource (lib "eagle-import") (part "R_0603"))
    )
    (comp (ref "R45")
      (value "510R 1%")
      (footprint "eagle-import:EIA0603")
      (libsource (lib "eagle-import") (part "R_0603"))
    )
    (comp (ref "R46")
      (value "510R 1%")
      (footprint "eagle-import:EIA0603")
      (libsource (lib "eagle-import") (part "R_0603"))
    )
    (comp (ref "R47")
      (value "10K 1%")
      (footprint "eagle-import:EIA0603")
      (libsource (lib "eagle-import") (part "R_0603"))
    )
    (comp (ref "R48")
      (value "10K 1%")
      (footprint "eagle-import:EIA0603")
      (libsource (lib "eagle-import") (part "R_0603"))
    )
    (comp (ref "R49")
      (value "100R 1%")
      (footprint "eagle-import:EIA0603")
      (libsource (lib "eagle-import") (part "R_0603"))
    )
    (comp (ref "R50")
      (value "10K 1%")
      (footprint "eagle-import:EIA0603")
      (libsource (lib "eagle-import") (part "R_0603"))
    )
    (comp (ref "R51")
      (value "10K 1%")
      (footprint "eagle-import:EIA0603")
      (libsource (lib "eagle-import") (part "R_0603"))
    )
    (comp (ref "R52")
      (value "10K 1%")
      (footprint "eagle-import:EIA0603")
      (libsource (lib "eagle-import") (part "R_0603"))
    )
    (comp (ref "R53")
      (value "n.P 1%")
      (footprint "eagle-import:EIA0603")
      (libsource (lib "eagle-import") (part "R_0603"))
    )
    (comp (ref "R54")
      (value "1.5K 1%")
      (footprint "eagle-import:EIA0603")
      (libsource (lib "eagle-import") (part "R_0603"))
    )
    (comp (ref "R55")
      (value "1.5K 1%")
      (footprint "eagle-import:EIA0603")
      (libsource (lib "eagle-import") (part "R_0603"))
    )
    (comp (ref "R56")
      (value "100R 1%")
      (footprint "eagle-import:EIA0603")
      (libsource (lib "eagle-import") (part "R_0603"))
    )
    (comp (ref "R57")
      (value "100R 1%")
      (footprint "eagle-import:EIA0603")
      (libsource (lib "eagle-import") (part "R_0603"))
    )
    (comp (ref "R58")
      (value "n.P 1%")
      (footprint "eagle-import:EIA0603")
      (libsource (lib "eagle-import") (part "R_0603"))
    )
    (comp (ref "R101")
      (value "33k 1%")
      (footprint "eagle-import:EIA0603")
      (libsource (lib "eagle-import") (part "R_0603"))
    )
    (comp (ref "R102")
      (value "33k 1%")
      (footprint "eagle-import:EIA0603")
      (libsource (lib "eagle-import") (part "R_0603"))
    )
    (comp (ref "D1")
      (value "SS14")
      (footprint "eagle-import:SMA")
      (fields (field (name "MFR") "MCC"))
      (libsource (lib "eagle-import") (part "SS14"))
    )
    (comp (ref "D2")
      (value "SS14")
      (footprint "eagle-import:SMA")
      (fields (field (name "MFR") "MCC"))
      (libsource (lib "eagle-import") (part "SS14"))
    )
    (comp (ref "D3")
      (value "MMBZ4696-HE3-18")
      (footprint "eagle-import:SOT23-3")
      (fields (field (name "MFR") "Vishay"))
      (libsource (lib "eagle-import") (part "MMBZ4696-HE3-18"))
    )
    (comp (ref "D4")
      (value "SS14")
      (footprint "eagle-import:SMA")
      (fields (field (name "MFR") "MCC"))
      (libsource (lib "eagle-import") (part "SS14"))
    )
    (comp (ref "D5")
      (value "MMBZ4696-HE3-18")
      (footprint "eagle-import:SOT23-3")
      (fields (field (name "MFR") "Vishay"))
      (libsource (lib "eagle-import") (part "MMBZ4696-HE3-18"))
    )
    (comp (ref "D6")
      (value "SS14")
      (footprint "eagle-import:SMA")
      (fields (field (name "MFR") "MCC"))
      (libsource (lib "eagle-import") (part "SS14"))
    )
    (comp (ref "D7")
      (value "MMBZ4696-HE3-18")
      (footprint "eagle-import:SOT23-3")
      (fields (field (name "MFR") "Vishay"))
      (libsource (lib "eagle-import") (part "MMBZ4696-HE3-18"))
    )
    (comp (ref "D14")
      (value "MMBZ4696-HE3-18")
      (footprint "eagle-import:SOT23-3")
      (fields (field (name "MFR") "Vishay"))
      (libsource (lib "eagle-import") (part "MMBZ4696-HE3-18"))
    )
    (comp (ref "K1")
      (value "RYA31012")
      (footprint "eagle-import:RYA31012")
      (fields (field (name "MFR") "TE Connectivity"))
      (libsource (lib "eagle-import") (part "RYA31012"))
    )
    (comp (ref "K2")
      (value "RYA31012")
      (footprint "eagle-import:RYA31012")
      (fields (field (name "MFR") "TE Connectivity"))
      (libsource (lib "eagle-import") (part "RYA31012"))
    )
    (comp (ref "Q2")
      (value "UT2955G-AA3-R")
      (footprint "eagle-import:SOT223")
      (fields (field (name "MFR") "UTC"))
      (libsource (lib "eagle-import") (part "UT2955G-AA3-R"))
    )
    (comp (ref "Q3")
      (value "2N7002")
      (footprint "eagle-import:SOT23")
      (fields (field (name "MFR") "Diodes, Guangdong Hotetech,NXP"))
      (libsource (lib "eagle-import") (part "2N7002"))
    )
    (comp (ref "Q4")
      (value "UT2955G-AA3-R")
      (footprint "eagle-import:SOT223")
      (fields (field (name "MFR") "UTC"))
      (libsource (lib "eagle-import") (part "UT2955G-AA3-R"))
    )
    (comp (ref "Q5")
      (value "2N7002")
      (footprint "eagle-import:SOT23")
      (fields (field (name "MFR") "Diodes, Guangdong Hotetech,NXP"))
      (libsource (lib "eagle-import") (part "2N7002"))
    )
    (comp (ref "Q6")
      (value "UT2955G-AA3-R")
      (footprint "eagle-import:SOT223")
      (fields (field (name "MFR") "UTC"))
      (libsource (lib "eagle-import") (part "UT2955G-AA3-R"))
    )
    (comp (ref "Q7")
      (value "2N7002")
      (footprint "eagle-import:SOT23")
      (fields (field (name "MFR") "Diodes, Guangdong Hotetech,NXP"))
      (libsource (lib "eagle-import") (part "2N7002"))
    )
    (comp (ref "Q8")
      (value "UT2955G-AA3-R")
      (footprint "eagle-import:SOT223")
      (fields (field (name "MFR") "UTC"))
      (libsource (lib "eagle-import") (part "UT2955G-AA3-R"))
    )
    (comp (ref "Q9")
      (value "2N7002")
      (footprint "eagle-import:SOT23")
      (fields (field (name "MFR") "Diodes, Guangdong Hotetech,NXP"))
      (libsource (lib "eagle-import") (part "2N7002"))
    )
    (comp (ref "R26")
      (value "10K 1%")
      (footprint "eagle-import:EIA0603")
      (libsource (lib "eagle-import") (part "R_0603"))
    )
    (comp (ref "R27")
      (value "10K 1%")
      (footprint "eagle-import:EIA0603")
      (libsource (lib "eagle-import") (part "R_0603"))
    )
    (comp (ref "R28")
      (value "10K 1%")
      (footprint "eagle-import:EIA0603")
      (libsource (lib "eagle-import") (part "R_0603"))
    )
    (comp (ref "R29")
      (value "100R 1%")
      (footprint "eagle-import:EIA0603")
      (libsource (lib "eagle-import") (part "R_0603"))
    )
    (comp (ref "R30")
      (value "10K 1%")
      (footprint "eagle-import:EIA0603")
      (libsource (lib "eagle-import") (part "R_0603"))
    )
    (comp (ref "R71")
      (value "10K 1%")
      (footprint "eagle-import:EIA0603")
      (libsource (lib "eagle-import") (part "R_0603"))
    )
    (comp (ref "R72")
      (value "10K 1%")
      (footprint "eagle-import:EIA0603")
      (libsource (lib "eagle-import") (part "R_0603"))
    )
    (comp (ref "R73")
      (value "10K 1%")
      (footprint "eagle-import:EIA0603")
      (libsource (lib "eagle-import") (part "R_0603"))
    )
    (comp (ref "R74")
      (value "100R 1%")
      (footprint "eagle-import:EIA0603")
      (libsource (lib "eagle-import") (part "R_0603"))
    )
    (comp (ref "R75")
      (value "10K 1%")
      (footprint "eagle-import:EIA0603")
      (libsource (lib "eagle-import") (part "R_0603"))
    )
    (comp (ref "R76")
      (value "10K 1%")
      (footprint "eagle-import:EIA0603")
      (libsource (lib "eagle-import") (part "R_0603"))
    )
    (comp (ref "R77")
      (value "100R 1%")
      (footprint "eagle-import:EIA0603")
      (libsource (lib "eagle-import") (part "R_0603"))
    )
    (comp (ref "R78")
      (value "10K 1%")
      (footprint "eagle-import:EIA0603")
      (libsource (lib "eagle-import") (part "R_0603"))
    )
    (comp (ref "R79")
      (value "10K 1%")
      (footprint "eagle-import:EIA0603")
      (libsource (lib "eagle-import") (part "R_0603"))
    )
    (comp (ref "R83")
      (value "10K 1%")
      (footprint "eagle-import:EIA0603")
      (libsource (lib "eagle-import") (part "R_0603"))
    )
    (comp (ref "R85")
      (value "100R 1%")
      (footprint "eagle-import:EIA0603")
      (libsource (lib "eagle-import") (part "R_0603"))
    )
    (comp (ref "R86")
      (value "10K 1%")
      (footprint "eagle-import:EIA0603")
      (libsource (lib "eagle-import") (part "R_0603"))
    )
    (comp (ref "R87")
      (value "10K 1%")
      (footprint "eagle-import:EIA0603")
      (libsource (lib "eagle-import") (part "R_0603"))
    )
    (comp (ref "R88")
      (value "10K 1%")
      (footprint "eagle-import:EIA0603")
      (libsource (lib "eagle-import") (part "R_0603"))
    )
    (comp (ref "R89")
      (value "10K 1%")
      (footprint "eagle-import:EIA0603")
      (libsource (lib "eagle-import") (part "R_0603"))
    )
    (comp (ref "V5")
      (value "B72205S0271K101B72205S2131K101")
      (footprint "eagle-import:EPCOS_B72205S0271K101_0")
      (fields (field (name "MFR") "EPCOS"))
      (libsource (lib "eagle-import") (part "B72205S0271K101B72205S2131K101"))
    )
    (comp (ref "V6")
      (value "B72205S0271K101B72205S2131K101")
      (footprint "eagle-import:EPCOS_B72205S0271K101_0")
      (fields (field (name "MFR") "EPCOS"))
      (libsource (lib "eagle-import") (part "B72205S0271K101B72205S2131K101"))
    )
    (comp (ref "C26")
      (value "100nF 100V")
      (footprint "eagle-import:EIA0603")
      (libsource (lib "eagle-import") (part "C_0603EIA0603"))
    )
    (comp (ref "C27")
      (value "100nF 100V")
      (footprint "eagle-import:EIA0603")
      (libsource (lib "eagle-import") (part "C_0603EIA0603"))
    )
    (comp (ref "C28")
      (value "R49AN347050B1M")
      (footprint "eagle-import:R49AN347050B1M")
      (fields (field (name "MFR") "Kemet"))
      (libsource (lib "eagle-import") (part "R49AN347050B1M"))
    )
    (comp (ref "C29")
      (value "100nF 100V")
      (footprint "eagle-import:EIA0603")
      (libsource (lib "eagle-import") (part "C_0603EIA0603"))
    )
    (comp (ref "C30")
      (value "100nF 100V")
      (footprint "eagle-import:EIA0603")
      (libsource (lib "eagle-import") (part "C_0603EIA0603"))
    )
    (comp (ref "C31")
      (value "100nF 100V")
      (footprint "eagle-import:EIA0603")
      (libsource (lib "eagle-import") (part "C_0603EIA0603"))
    )
    (comp (ref "C32")
      (value "50PX470MEFC10X20")
      (footprint "eagle-import:CAPACITOR-ELKO-RM5-10X16")
      (fields (field (name "MFR") "Rubicon"))
      (libsource (lib "eagle-import") (part "50PX470MEFC10X20"))
    )
    (comp (ref "C33")
      (value "50PX470MEFC10X20")
      (footprint "eagle-import:CAPACITOR-ELKO-RM5-10X16")
      (fields (field (name "MFR") "Rubicon"))
      (libsource (lib "eagle-import") (part "50PX470MEFC10X20"))
    )
    (comp (ref "C34")
      (value "50PX470MEFC10X20")
      (footprint "eagle-import:CAPACITOR-ELKO-RM5-10X16")
      (fields (field (name "MFR") "Rubicon"))
      (libsource (lib "eagle-import") (part "50PX470MEFC10X20"))
    )
    (comp (ref "F1")
      (value "696101000002")
      (footprint "eagle-import:FUSE_RM22.6")
      (fields (field (name "MFR") "Wurth Elektronik"))
      (libsource (lib "eagle-import") (part "696101000002"))
    )
    (comp (ref "J2")
      (value "61300411121")
      (footprint "eagle-import:X04_100MIL_1ROW")
      (fields (field (name "MFR") "Wurth Electronics"))
      (libsource (lib "eagle-import") (part "61300411121"))
    )
    (comp (ref "R22")
      (value "10k 1%")
      (footprint "eagle-import:EIA0603")
      (libsource (lib "eagle-import") (part "R_0603"))
    )
    (comp (ref "R25")
      (value "10k 1%")
      (footprint "eagle-import:EIA0603")
      (libsource (lib "eagle-import") (part "R_0603"))
    )
    (comp (ref "R80")
      (value "10k 1%")
      (footprint "eagle-import:EIA0603")
      (libsource (lib "eagle-import") (part "R_0603"))
    )
    (comp (ref "R81")
      (value "RNF12FTD10M0")
      (footprint "eagle-import:RES-RM12.5-VR37")
      (fields (field (name "MFR") "Stackpole Electronics Inc"))
      (libsource (lib "eagle-import") (part "RNF12FTD10M0"))
    )
    (comp (ref "R82")
      (value "RNF12FTD10M0")
      (footprint "eagle-import:RES-RM12.5-VR37")
      (fields (field (name "MFR") "Stackpole Electronics Inc"))
      (libsource (lib "eagle-import") (part "RNF12FTD10M0"))
    )
    (comp (ref "R84")
      (value "10k 1%")
      (footprint "eagle-import:EIA0603")
      (libsource (lib "eagle-import") (part "R_0603"))
    )
    (comp (ref "V4")
      (value "0603ESDA-24NSMD")
      (footprint "eagle-import:EIA0603")
      (fields (field (name "MFR") "Bourns"))
      (libsource (lib "eagle-import") (part "0603ESDA-24NSMD"))
    )
    (comp (ref "V7")
      (value "B72205S0271K101B72205S2131K101")
      (footprint "eagle-import:EPCOS_B72205S0271K101_0")
      (fields (field (name "MFR") "EPCOS"))
      (libsource (lib "eagle-import") (part "B72205S0271K101B72205S2131K101"))
    )
    (comp (ref "V8")
      (value "0603ESDA-24NSMD")
      (footprint "eagle-import:EIA0603")
      (fields (field (name "MFR") "Bourns"))
      (libsource (lib "eagle-import") (part "0603ESDA-24NSMD"))
    )
    (comp (ref "X1")
      (value "B2B-XH-AM(LF)(SN)")
      (footprint "eagle-import:B2B-XH-AM(LF)(SN)")
      (fields (field (name "MFR") "JST"))
      (libsource (lib "eagle-import") (part "B2B-XH-AM(LF)(SN)"))
    )
    (comp (ref "X2")
      (value "B2B-XH-AM(LF)(SN)")
      (footprint "eagle-import:B2B-XH-AM(LF)(SN)")
      (fields (field (name "MFR") "JST"))
      (libsource (lib "eagle-import") (part "B2B-XH-AM(LF)(SN)"))
    )
    (comp (ref "X4")
      (value "282834-2")
      (footprint "eagle-import:TE_282834-2_0")
      (fields (field (name "MFR") "TE"))
      (libsource (lib "eagle-import") (part "282834-2"))
    )
    (comp (ref "X5")
      (value "726386-2TE_726386-2")
      (footprint "eagle-import:TE_726386-2")
      (fields
        (field (name "DIGIKEY_PART_NUMBER") "A114371-ND")
        (field (name "MF") "TE")
        (field (name "MOUSER_PART_NUMBER") "571-726386-2")
      )
      (libsource (lib "eagle-import") (part "726386-2TE_726386-2"))
    )
    (comp (ref "X6")
      (value "282834-2")
      (footprint "eagle-import:TE_282834-2_0")
      (fields (field (name "MFR") "TE"))
      (libsource (lib "eagle-import") (part "282834-2"))
    )
    (comp (ref "X7")
      (value "726386-2TE_726386-2")
      (footprint "eagle-import:TE_726386-2")
      (fields
        (field (name "DIGIKEY_PART_NUMBER") "A114371-ND")
        (field (name "MF") "TE")
        (field (name "MOUSER_PART_NUMBER") "571-726386-2")
      )
      (libsource (lib "eagle-import") (part "726386-2TE_726386-2"))
    )
    (comp (ref "X10")
      (value "MOLEX_206832-0601MOLEX_206832-0601")
      (footprint "eagle-import:MOLEX_206832-0601")
      (fields (field (name "MFR") "Molex"))
      (libsource (lib "eagle-import") (part "MOLEX_206832-0601MOLEX_206832-0601"))
    )
    (comp (ref "X11")
      (value "726386-2TE_726386-2")
      (footprint "eagle-import:TE_726386-2")
      (fields
        (field (name "DIGIKEY_PART_NUMBER") "A114371-ND")
        (field (name "MF") "TE")
        (field (name "MOUSER_PART_NUMBER") "571-726386-2")
      )
      (libsource (lib "eagle-import") (part "726386-2TE_726386-2"))
    )
    (comp (ref "X12")
      (value "726386-2TE_726386-2")
      (footprint "eagle-import:TE_726386-2")
      (fields
        (field (name "DIGIKEY_PART_NUMBER") "A114371-ND")
        (field (name "MF") "TE")
        (field (name "MOUSER_PART_NUMBER") "571-726386-2")
      )
      (libsource (lib "eagle-import") (part "726386-2TE_726386-2"))
    )
    (comp (ref "X13")
      (value "726386-2TE_726386-2")
      (footprint "eagle-import:TE_726386-2")
      (fields
        (field (name "DIGIKEY_PART_NUMBER") "A114371-ND")
        (field (name "MF") "TE")
        (field (name "MOUSER_PART_NUMBER") "571-726386-2")
      )
      (libsource (lib "eagle-import") (part "726386-2TE_726386-2"))
    )
    (comp (ref "X14")
      (value "726386-2TE_726386-2")
      (footprint "eagle-import:TE_726386-2")
      (fields
        (field (name "DIGIKEY_PART_NUMBER") "A114371-ND")
        (field (name "MF") "TE")
        (field (name "MOUSER_PART_NUMBER") "571-726386-2")
      )
      (libsource (lib "eagle-import") (part "726386-2TE_726386-2"))
    )
    (comp (ref "X15")
      (value "726386-2TE_726386-2")
      (footprint "eagle-import:TE_726386-2")
      (fields
        (field (name "DIGIKEY_PART_NUMBER") "A114371-ND")
        (field (name "MF") "TE")
        (field (name "MOUSER_PART_NUMBER") "571-726386-2")
      )
      (libsource (lib "eagle-import") (part "726386-2TE_726386-2"))
    )
    (comp (ref "X16")
      (value "726386-2TE_726386-2")
      (footprint "eagle-import:TE_726386-2")
      (fields
        (field (name "DIGIKEY_PART_NUMBER") "A114371-ND")
        (field (name "MF") "TE")
        (field (name "MOUSER_PART_NUMBER") "571-726386-2")
      )
      (libsource (lib "eagle-import") (part "726386-2TE_726386-2"))
    )
    (comp (ref "X19")
      (value "726386-2TE_726386-2")
      (footprint "eagle-import:TE_726386-2")
      (fields
        (field (name "DIGIKEY_PART_NUMBER") "A114371-ND")
        (field (name "MF") "TE")
        (field (name "MOUSER_PART_NUMBER") "571-726386-2")
      )
      (libsource (lib "eagle-import") (part "726386-2TE_726386-2"))
    )
    (comp (ref "X20")
      (value "726386-2TE_726386-2")
      (footprint "eagle-import:TE_726386-2")
      (fields
        (field (name "DIGIKEY_PART_NUMBER") "A114371-ND")
        (field (name "MF") "TE")
        (field (name "MOUSER_PART_NUMBER") "571-726386-2")
      )
      (libsource (lib "eagle-import") (part "726386-2TE_726386-2"))
    )
    (comp (ref "X21")
      (value "726386-2TE_726386-2")
      (footprint "eagle-import:TE_726386-2")
      (fields
        (field (name "DIGIKEY_PART_NUMBER") "A114371-ND")
        (field (name "MF") "TE")
        (field (name "MOUSER_PART_NUMBER") "571-726386-2")
      )
      (libsource (lib "eagle-import") (part "726386-2TE_726386-2"))
    )
    (comp (ref "X22")
      (value "726386-2TE_726386-2")
      (footprint "eagle-import:TE_726386-2")
      (fields
        (field (name "DIGIKEY_PART_NUMBER") "A114371-ND")
        (field (name "MF") "TE")
        (field (name "MOUSER_PART_NUMBER") "571-726386-2")
      )
      (libsource (lib "eagle-import") (part "726386-2TE_726386-2"))
    )
    (comp (ref "X23")
      (value "282834-2")
      (footprint "eagle-import:TE_282834-2_0")
      (fields (field (name "MFR") "TE"))
      (libsource (lib "eagle-import") (part "282834-2"))
    )
  )
  (nets
    (net (code "1") (name "AIR_PUMP+") (class "Default")
      (node (ref "D1") (pin "1") (pinfunction "C_1") (pintype "passive"))
      (node (ref "Q2") (pin "2") (pinfunction "DRAIN_2") (pintype "passive"))
      (node (ref "Q2") (pin "4") (pinfunction "DRAIN_4") (pintype "passive"))
      (node (ref "R30") (pin "2") (pinfunction "2_2") (pintype "passive"))
      (node (ref "X5") (pin "1") (pinfunction "1_1") (pintype "passive"))
      (node (ref "X5") (pin "1-2") (pinfunction "1_1-2") (pintype "passive"))
    )
    (net (code "2") (name "AI_O2_SENSOR1") (class "Default")
      (node (ref "C22") (pin "2") (pinfunction "2_2") (pintype "passive"))
      (node (ref "IC1") (pin "17") (pinfunction "PA0_17") (pintype "bidirectional"))
      (node (ref "R38") (pin "1") (pinfunction "1_1") (pintype "passive"))
      (node (ref "R39") (pin "1") (pinfunction "1_1") (pintype "passive"))
      (node (ref "R44") (pin "1") (pinfunction "1_1") (pintype "passive"))
    )
    (net (code "3") (name "AI_O2_SENSOR2") (class "Default")
      (node (ref "C23") (pin "2") (pinfunction "2_2") (pintype "passive"))
      (node (ref "IC1") (pin "18") (pinfunction "PA1_18") (pintype "bidirectional"))
      (node (ref "R52") (pin "1") (pinfunction "1_1") (pintype "passive"))
      (node (ref "R53") (pin "1") (pinfunction "1_1") (pintype "passive"))
      (node (ref "R58") (pin "1") (pinfunction "1_1") (pintype "passive"))
    )
    (net (code "4") (name "CO2_SCL") (class "Default")
      (node (ref "IC1") (pin "13") (pinfunction "PC0_13") (pintype "bidirectional"))
      (node (ref "R21") (pin "1") (pinfunction "1_1") (pintype "passive"))
      (node (ref "R60") (pin "1") (pinfunction "1_1") (pintype "passive"))
      (node (ref "R63") (pin "1") (pinfunction "1_1") (pintype "passive"))
      (node (ref "R68") (pin "1") (pinfunction "1_1") (pintype "passive"))
    )
    (net (code "5") (name "CO2_SDA") (class "Default")
      (node (ref "IC1") (pin "14") (pinfunction "PC1_14") (pintype "bidirectional"))
      (node (ref "R20") (pin "1") (pinfunction "1_1") (pintype "passive"))
      (node (ref "R59") (pin "1") (pinfunction "1_1") (pintype "passive"))
      (node (ref "R62") (pin "1") (pinfunction "1_1") (pintype "passive"))
      (node (ref "R67") (pin "1") (pinfunction "1_1") (pintype "passive"))
    )
    (net (code "6") (name "DGB_SWDCLK_TCK") (class "Default")
      (node (ref "IC1") (pin "46") (pinfunction "PA14-BOOT0_46") (pintype "bidirectional"))
      (node (ref "R17") (pin "2") (pinfunction "2_2") (pintype "passive"))
    )
    (net (code "7") (name "DGB_SWDIO_TMS") (class "Default")
      (node (ref "IC1") (pin "45") (pinfunction "PA13_45") (pintype "bidirectional"))
      (node (ref "R16") (pin "2") (pinfunction "2_2") (pintype "passive"))
    )
    (net (code "8") (name "DI_PULSE1") (class "Default")
      (node (ref "IC1") (pin "37") (pinfunction "PA9_37") (pintype "bidirectional"))
      (node (ref "R15") (pin "1") (pinfunction "1_1") (pintype "passive"))
    )
    (net (code "9") (name "DI_PUSHBUTTON1") (class "Default")
      (node (ref "IC1") (pin "27") (pinfunction "PB0_27") (pintype "bidirectional"))
      (node (ref "R22") (pin "1") (pinfunction "1_1") (pintype "passive"))
    )
    (net (code "10") (name "DI_PUSHBUTTON2") (class "Default")
      (node (ref "IC1") (pin "26") (pinfunction "PC5_26") (pintype "bidirectional"))
      (node (ref "R84") (pin "1") (pinfunction "1_1") (pintype "passive"))
    )
    (net (code "11") (name "DI_USART_RX") (class "Default")
      (node (ref "IC1") (pin "1") (pinfunction "PC11_1") (pintype "bidirectional"))
      (node (ref "R95") (pin "2") (pinfunction "2_2") (pintype "passive"))
    )
    (net (code "12") (name "DO_AIR_PUMP_ON") (class "Default")
      (node (ref "IC1") (pin "48") (pinfunction "PC8_48") (pintype "bidirectional"))
      (node (ref "R29") (pin "2") (pinfunction "2_2") (pintype "passive"))
    )
    (net (code "13") (name "DO_FAN_ON") (class "Default")
      (node (ref "IC1") (pin "51") (pinfunction "PD1_51") (pintype "bidirectional"))
      (node (ref "R85") (pin "2") (pinfunction "2_2") (pintype "passive"))
    )
    (net (code "14") (name "DO_HEATER_ON") (class "Default")
      (node (ref "IC1") (pin "2") (pinfunction "PC12_2") (pintype "bidirectional"))
      (node (ref "R74") (pin "2") (pinfunction "2_2") (pintype "passive"))
    )
    (net (code "15") (name "DO_HUMIDIFIER_ON") (class "Default")
      (node (ref "IC1") (pin "3") (pinfunction "PC13_3") (pintype "bidirectional"))
      (node (ref "R77") (pin "2") (pinfunction "2_2") (pintype "passive"))
    )
    (net (code "16") (name "DO_IR_TX") (class "Default")
      (node (ref "IC1") (pin "36") (pinfunction "PA8_36") (pintype "bidirectional"))
      (node (ref "R3") (pin "2") (pinfunction "2_2") (pintype "passive"))
    )
    (net (code "17") (name "DO_USART_TX") (class "Default")
      (node (ref "IC1") (pin "64") (pinfunction "PC10_64") (pintype "bidirectional"))
      (node (ref "R98") (pin "2") (pinfunction "2_2") (pintype "passive"))
    )
    (net (code "18") (name "DO_USART_TX_EN") (class "Default")
      (node (ref "IC1") (pin "47") (pinfunction "PA15_47") (pintype "bidirectional"))
      (node (ref "R97") (pin "2") (pinfunction "2_2") (pintype "passive"))
    )
    (net (code "19") (name "FAN+") (class "Default")
      (node (ref "D6") (pin "1") (pinfunction "C_1") (pintype "passive"))
      (node (ref "Q8") (pin "2") (pinfunction "DRAIN_2") (pintype "passive"))
      (node (ref "Q8") (pin "4") (pinfunction "DRAIN_4") (pintype "passive"))
      (node (ref "R89") (pin "2") (pinfunction "2_2") (pintype "passive"))
      (node (ref "X23") (pin "1") (pinfunction "1_1") (pintype "bidirectional"))
    )
    (net (code "20") (name "GND") (class "Default")
      (node (ref "C1") (pin "1") (pinfunction "1_1") (pintype "passive"))
      (node (ref "C10") (pin "2") (pinfunction "2_2") (pintype "passive"))
      (node (ref "C12") (pin "2") (pinfunction "2_2") (pintype "passive"))
      (node (ref "C13") (pin "1") (pinfunction "1_1") (pintype "passive"))
      (node (ref "C14") (pin "2") (pinfunction "2_2") (pintype "passive"))
      (node (ref "C15") (pin "2") (pinfunction "2_2") (pintype "passive"))
      (node (ref "C16") (pin "2") (pinfunction "2_2") (pintype "passive"))
      (node (ref "C18") (pin "2") (pinfunction "2_2") (pintype "passive"))
      (node (ref "C19") (pin "1") (pinfunction "1_1") (pintype "passive"))
      (node (ref "C2") (pin "1") (pinfunction "1_1") (pintype "passive"))
      (node (ref "C20") (pin "2") (pinfunction "2_2") (pintype "passive"))
      (node (ref "C21") (pin "2") (pinfunction "2_2") (pintype "passive"))
      (node (ref "C22") (pin "1") (pinfunction "1_1") (pintype "passive"))
      (node (ref "C23") (pin "1") (pinfunction "1_1") (pintype "passive"))
      (node (ref "C24") (pin "1") (pinfunction "1_1") (pintype "passive"))
      (node (ref "C25") (pin "1") (pinfunction "1_1") (pintype "passive"))
      (node (ref "C26") (pin "2") (pinfunction "2_2") (pintype "passive"))
      (node (ref "C27") (pin "2") (pinfunction "2_2") (pintype "passive"))
      (node (ref "C29") (pin "2") (pinfunction "2_2") (pintype "passive"))
      (node (ref "C3") (pin "2") (pinfunction "2_2") (pintype "passive"))
      (node (ref "C30") (pin "2") (pinfunction "2_2") (pintype "passive"))
      (node (ref "C31") (pin "2") (pinfunction "2_2") (pintype "passive"))
      (node (ref "C32") (pin "2") (pinfunction "-_2") (pintype "passive"))
      (node (ref "C33") (pin "2") (pinfunction "-_2") (pintype "passive"))
      (node (ref "C34") (pin "2") (pinfunction "-_2") (pintype "passive"))
      (node (ref "C35") (pin "1") (pinfunction "1_1") (pintype "passive"))
      (node (ref "C36") (pin "2") (pinfunction "2_2") (pintype "passive"))
      (node (ref "C37") (pin "2") (pinfunction "2_2") (pintype "passive"))
      (node (ref "C4") (pin "1") (pinfunction "1_1") (pintype "passive"))
      (node (ref "C5") (pin "1") (pinfunction "1_1") (pintype "passive"))
      (node (ref "C6") (pin "2") (pinfunction "2_2") (pintype "passive"))
      (node (ref "C7") (pin "2") (pinfunction "2_2") (pintype "passive"))
      (node (ref "C8") (pin "2") (pinfunction "2_2") (pintype "passive"))
      (node (ref "C9") (pin "2") (pinfunction "2_2") (pintype "passive"))
      (node (ref "D1") (pin "2") (pinfunction "A_2") (pintype "passive"))
      (node (ref "D2") (pin "2") (pinfunction "A_2") (pintype "passive"))
      (node (ref "D4") (pin "2") (pinfunction "A_2") (pintype "passive"))
      (node (ref "D6") (pin "2") (pinfunction "A_2") (pintype "passive"))
      (node (ref "IC1") (pin "9") (pinfunction "VSS/VSSA_9") (pintype "bidirectional"))
      (node (ref "IC2") (pin "2") (pinfunction "GND_2") (pintype "power_in"))
      (node (ref "IC4") (pin "2") (pinfunction "VEE_2") (pintype "passive"))
      (node (ref "IC5") (pin "2") (pinfunction "VEE_2") (pintype "passive"))
      (node (ref "IC6") (pin "2") (pinfunction "VEE_2") (pintype "passive"))
      (node (ref "IC7") (pin "2") (pinfunction "VEE_2") (pintype "passive"))
      (node (ref "IC8") (pin "2") (pinfunction "VEE_2") (pintype "passive"))
      (node (ref "IC9") (pin "2") (pinfunction "VEE_2") (pintype "passive"))
      (node (ref "J1") (pin "5") (pinfunction "GND_5") (pintype "power_in"))
      (node (ref "J1") (pin "SH1") (pinfunction "SHIELD1_SH1") (pintype "passive"))
      (node (ref "J1") (pin "SH2") (pinfunction "SHIELD2_SH2") (pintype "passive"))
      (node (ref "J1") (pin "SH3") (pinfunction "SHIELD3_SH3") (pintype "passive"))
      (node (ref "J1") (pin "SH4") (pinfunction "SHIELD4_SH4") (pintype "passive"))
      (node (ref "J1") (pin "SH5") (pinfunction "SHIELD5_SH5") (pintype "passive"))
      (node (ref "J1") (pin "SH6") (pinfunction "SHIELD6_SH6") (pintype "passive"))
      (node (ref "J2") (pin "03") (pinfunction "03_03") (pintype "passive"))
      (node (ref "J3") (pin "8") (pinfunction "8_8") (pintype "passive"))
      (node (ref "J4") (pin "04") (pinfunction "04_04") (pintype "passive"))
      (node (ref "K1") (pin "A1") (pinfunction "1_A1") (pintype "passive"))
      (node (ref "K2") (pin "A1") (pinfunction "1_A1") (pintype "passive"))
      (node (ref "Q1") (pin "2") (pinfunction "E_2") (pintype "passive"))
      (node (ref "Q3") (pin "2") (pinfunction "S_2") (pintype "passive"))
      (node (ref "Q5") (pin "2") (pinfunction "S_2") (pintype "passive"))
      (node (ref "Q7") (pin "2") (pinfunction "S_2") (pintype "passive"))
      (node (ref "Q9") (pin "2") (pinfunction "S_2") (pintype "passive"))
      (node (ref "R1") (pin "2") (pinfunction "2_2") (pintype "passive"))
      (node (ref "R101") (pin "2") (pinfunction "2_2") (pintype "passive"))
      (node (ref "R102") (pin "2") (pinfunction "2_2") (pintype "passive"))
      (node (ref "R11") (pin "2") (pinfunction "2_2") (pintype "passive"))
      (node (ref "R12") (pin "1") (pinfunction "1_1") (pintype "passive"))
      (node (ref "R28") (pin "1") (pinfunction "1_1") (pintype "passive"))
      (node (ref "R30") (pin "1") (pinfunction "1_1") (pintype "passive"))
      (node (ref "R31") (pin "1") (pinfunction "1_1") (pintype "passive"))
      (node (ref "R39") (pin "2") (pinfunction "2_2") (pintype "passive"))
      (node (ref "R4") (pin "2") (pinfunction "2_2") (pintype "passive"))
      (node (ref "R45") (pin "1") (pinfunction "1_1") (pintype "passive"))
      (node (ref "R53") (pin "2") (pinfunction "2_2") (pintype "passive"))
      (node (ref "R61") (pin "1") (pinfunction "1_1") (pintype "passive"))
      (node (ref "R64") (pin "2") (pinfunction "2_2") (pintype "passive"))
      (node (ref "R65") (pin "2") (pinfunction "2_2") (pintype "passive"))
      (node (ref "R66") (pin "1") (pinfunction "1_1") (pintype "passive"))
      (node (ref "R69") (pin "2") (pinfunction "2_2") (pintype "passive"))
      (node (ref "R70") (pin "2") (pinfunction "2_2") (pintype "passive"))
      (node (ref "R71") (pin "1") (pinfunction "1_1") (pintype "passive"))
      (node (ref "R72") (pin "1") (pinfunction "1_1") (pintype "passive"))
      (node (ref "R78") (pin "1") (pinfunction "1_1") (pintype "passive"))
      (node (ref "R79") (pin "1") (pinfunction "1_1") (pintype "passive"))
      (node (ref "R8") (pin "1") (pinfunction "1_1") (pintype "passive"))
      (node (ref "R82") (pin "1") (pinfunction "1_1") (pintype "passive"))
      (node (ref "R88") (pin "1") (pinfunction "1_1") (pintype "passive"))
      (node (ref "R89") (pin "1") (pinfunction "1_1") (pintype "passive"))
      (node (ref "R92") (pin "1") (pinfunction "1_1") (pintype "passive"))
      (node (ref "R94") (pin "1") (pinfunction "1_1") (pintype "passive"))
      (node (ref "V1") (pin "1") (pinfunction "1_1") (pintype "passive"))
      (node (ref "V10") (pin "1") (pinfunction "1_1") (pintype "passive"))
      (node (ref "V2") (pin "1") (pinfunction "1_1") (pintype "passive"))
      (node (ref "V4") (pin "2") (pinfunction "2_2") (pintype "passive"))
      (node (ref "V8") (pin "2") (pinfunction "2_2") (pintype "passive"))
      (node (ref "V9") (pin "1") (pinfunction "1_1") (pintype "passive"))
      (node (ref "X10") (pin "5") (pinfunction "5_5") (pintype "passive"))
      (node (ref "X23") (pin "2") (pinfunction "2_2") (pintype "bidirectional"))
      (node (ref "X3") (pin "4") (pinfunction "4_4") (pintype "bidirectional"))
      (node (ref "X4") (pin "2") (pinfunction "2_2") (pintype "bidirectional"))
      (node (ref "X6") (pin "2") (pinfunction "2_2") (pintype "bidirectional"))
      (node (ref "X7") (pin "1") (pinfunction "1_1") (pintype "passive"))
      (node (ref "X7") (pin "1-2") (pinfunction "1_1-2") (pintype "passive"))
      (node (ref "X8") (pin "4") (pinfunction "4_4") (pintype "passive"))
      (node (ref "X9") (pin "4") (pinfunction "4_4") (pintype "passive"))
    )
    (net (code "21") (name "HEATER_MAINS_L_SW") (class "Default")
      (node (ref "K1") (pin "14") (pinfunction "3_14") (pintype "passive"))
      (node (ref "V6") (pin "2") (pinfunction "2_2") (pintype "passive"))
      (node (ref "X11") (pin "1") (pinfunction "1_1") (pintype "passive"))
      (node (ref "X11") (pin "1-2") (pinfunction "1_1-2") (pintype "passive"))
    )
    (net (code "22") (name "HUMIDIFIER_MAINS_L_SW") (class "Default")
      (node (ref "K2") (pin "14") (pinfunction "3_14") (pintype "passive"))
      (node (ref "V5") (pin "2") (pinfunction "2_2") (pintype "passive"))
      (node (ref "X13") (pin "1") (pinfunction "1_1") (pintype "passive"))
      (node (ref "X13") (pin "1-2") (pinfunction "1_1-2") (pintype "passive"))
    )
    (net (code "23") (name "IR_DIODE_A") (class "Default")
      (node (ref "R5") (pin "1") (pinfunction "1_1") (pintype "passive"))
      (node (ref "R6") (pin "2") (pinfunction "2_2") (pintype "passive"))
      (node (ref "X2") (pin "2") (pinfunction "2_2") (pintype "bidirectional"))
    )
    (net (code "24") (name "IR_DIODE_C") (class "Default")
      (node (ref "Q1") (pin "3") (pinfunction "C_3") (pintype "passive"))
      (node (ref "R5") (pin "2") (pinfunction "2_2") (pintype "passive"))
      (node (ref "X2") (pin "1") (pinfunction "1_1") (pintype "bidirectional"))
    )
    (net (code "25") (name "IR_TR_NPN_C") (class "Default")
      (node (ref "R13") (pin "1") (pinfunction "1_1") (pintype "passive"))
      (node (ref "R9") (pin "1") (pinfunction "1_1") (pintype "passive"))
      (node (ref "V3") (pin "2") (pinfunction "2_2") (pintype "passive"))
      (node (ref "X1") (pin "2") (pinfunction "2_2") (pintype "bidirectional"))
    )
    (net (code "26") (name "IR_TR_NPN_E") (class "Default")
      (node (ref "R12") (pin "2") (pinfunction "2_2") (pintype "passive"))
      (node (ref "R7") (pin "1") (pinfunction "1_1") (pintype "passive"))
      (node (ref "V3") (pin "1") (pinfunction "1_1") (pintype "passive"))
      (node (ref "X1") (pin "1") (pinfunction "1_1") (pintype "bidirectional"))
    )
    (net (code "27") (name "LCD_SCL") (class "Default")
      (node (ref "IC1") (pin "24") (pinfunction "PA7_24") (pintype "bidirectional"))
      (node (ref "J2") (pin "01") (pinfunction "01_01") (pintype "passive"))
      (node (ref "R23") (pin "1") (pinfunction "1_1") (pintype "passive"))
    )
    (net (code "28") (name "LCD_SDA") (class "Default")
      (node (ref "IC1") (pin "23") (pinfunction "PA6_23") (pintype "bidirectional"))
      (node (ref "J2") (pin "02") (pinfunction "02_02") (pintype "passive"))
      (node (ref "R24") (pin "1") (pinfunction "1_1") (pintype "passive"))
    )
    (net (code "29") (name "MAINS_L") (class "Default")
      (node (ref "X19") (pin "1") (pinfunction "1_1") (pintype "passive"))
      (node (ref "X19") (pin "1-2") (pinfunction "1_1-2") (pintype "passive"))
      (node (ref "X21") (pin "1") (pinfunction "1_1") (pintype "passive"))
      (node (ref "X21") (pin "1-2") (pinfunction "1_1-2") (pintype "passive"))
    )
    (net (code "30") (name "MAINS_L_F") (class "Default")
      (node (ref "C28") (pin "1") (pinfunction "1_1") (pintype "passive"))
      (node (ref "F1") (pin "2") (pinfunction "P$2_2") (pintype "bidirectional"))
      (node (ref "K1") (pin "11") (pinfunction "4_11") (pintype "passive"))
      (node (ref "K2") (pin "11") (pinfunction "4_11") (pintype "passive"))
      (node (ref "V5") (pin "1") (pinfunction "1_1") (pintype "passive"))
      (node (ref "V6") (pin "1") (pinfunction "1_1") (pintype "passive"))
      (node (ref "V7") (pin "2") (pinfunction "2_2") (pintype "passive"))
    )
    (net (code "31") (name "MAINS_L_SW") (class "Default")
      (node (ref "F1") (pin "1") (pinfunction "P$1_1") (pintype "bidirectional"))
      (node (ref "X16") (pin "1") (pinfunction "1_1") (pintype "passive"))
      (node (ref "X16") (pin "1-2") (pinfunction "1_1-2") (pintype "passive"))
    )
    (net (code "32") (name "MAINS_N_SW") (class "Default")
      (node (ref "C28") (pin "2") (pinfunction "2_2") (pintype "passive"))
      (node (ref "R81") (pin "2") (pinfunction "2_2") (pintype "passive"))
      (node (ref "V7") (pin "1") (pinfunction "1_1") (pintype "passive"))
      (node (ref "X12") (pin "1") (pinfunction "1_1") (pintype "passive"))
      (node (ref "X12") (pin "1-2") (pinfunction "1_1-2") (pintype "passive"))
      (node (ref "X14") (pin "1") (pinfunction "1_1") (pintype "passive"))
      (node (ref "X14") (pin "1-2") (pinfunction "1_1-2") (pintype "passive"))
      (node (ref "X15") (pin "1") (pinfunction "1_1") (pintype "passive"))
      (node (ref "X15") (pin "1-2") (pinfunction "1_1-2") (pintype "passive"))
    )
    (net (code "33") (name "MAINS_N_TO_SW") (class "Default")
      (node (ref "X20") (pin "1") (pinfunction "1_1") (pintype "passive"))
      (node (ref "X20") (pin "1-2") (pinfunction "1_1-2") (pintype "passive"))
      (node (ref "X22") (pin "1") (pinfunction "1_1") (pintype "passive"))
      (node (ref "X22") (pin "1-2") (pinfunction "1_1-2") (pintype "passive"))
    )
    (net (code "34") (name "NRST") (class "Default")
      (node (ref "C5") (pin "2") (pinfunction "2_2") (pintype "passive"))
      (node (ref "IC1") (pin "12") (pinfunction "PF2-NRST_12") (pintype "bidirectional"))
      (node (ref "R18") (pin "2") (pinfunction "2_2") (pintype "passive"))
      (node (ref "R19") (pin "1") (pinfunction "1_1") (pintype "passive"))
    )
    (net (code "35") (name "Net-(C11-Pad2)") (class "Default")
      (node (ref "C11") (pin "2") (pinfunction "2_2") (pintype "passive"))
      (node (ref "R33") (pin "1") (pinfunction "1_1") (pintype "passive"))
      (node (ref "R34") (pin "2") (pinfunction "2_2") (pintype "passive"))
    )
    (net (code "36") (name "Net-(C13-Pad2)") (class "Default")
      (node (ref "C13") (pin "2") (pinfunction "2_2") (pintype "passive"))
      (node (ref "R40") (pin "2") (pinfunction "2_2") (pintype "passive"))
      (node (ref "R41") (pin "1") (pinfunction "1_1") (pintype "passive"))
    )
    (net (code "37") (name "Net-(C14-Pad1)") (class "Default")
      (node (ref "C14") (pin "1") (pinfunction "1_1") (pintype "passive"))
      (node (ref "R42") (pin "2") (pinfunction "2_2") (pintype "passive"))
      (node (ref "R43") (pin "1") (pinfunction "1_1") (pintype "passive"))
    )
    (net (code "38") (name "Net-(C17-Pad2)") (class "Default")
      (node (ref "C17") (pin "2") (pinfunction "2_2") (pintype "passive"))
      (node (ref "R47") (pin "1") (pinfunction "1_1") (pintype "passive"))
      (node (ref "R48") (pin "2") (pinfunction "2_2") (pintype "passive"))
    )
    (net (code "39") (name "Net-(C19-Pad2)") (class "Default")
      (node (ref "C19") (pin "2") (pinfunction "2_2") (pintype "passive"))
      (node (ref "R54") (pin "2") (pinfunction "2_2") (pintype "passive"))
      (node (ref "R57") (pin "1") (pinfunction "1_1") (pintype "passive"))
    )
    (net (code "40") (name "Net-(C20-Pad1)") (class "Default")
      (node (ref "C20") (pin "1") (pinfunction "1_1") (pintype "passive"))
      (node (ref "R55") (pin "2") (pinfunction "2_2") (pintype "passive"))
      (node (ref "R56") (pin "1") (pinfunction "1_1") (pintype "passive"))
    )
    (net (code "41") (name "Net-(C35-Pad2)") (class "Default")
      (node (ref "C35") (pin "2") (pinfunction "2_2") (pintype "passive"))
      (node (ref "R100") (pin "1") (pinfunction "1_1") (pintype "passive"))
      (node (ref "R99") (pin "1") (pinfunction "1_1") (pintype "passive"))
    )
    (net (code "42") (name "Net-(D2-C)") (class "Default")
      (node (ref "D2") (pin "1") (pinfunction "C_1") (pintype "passive"))
      (node (ref "K1") (pin "A2") (pinfunction "2_A2") (pintype "passive"))
      (node (ref "Q4") (pin "2") (pinfunction "DRAIN_2") (pintype "passive"))
      (node (ref "Q4") (pin "4") (pinfunction "DRAIN_4") (pintype "passive"))
      (node (ref "R72") (pin "2") (pinfunction "2_2") (pintype "passive"))
    )
    (net (code "43") (name "Net-(D3-A)") (class "Default")
      (node (ref "D3") (pin "1") (pinfunction "A_1") (pintype "passive"))
      (node (ref "Q4") (pin "1") (pinfunction "GATE_1") (pintype "passive"))
      (node (ref "R73") (pin "1") (pinfunction "1_1") (pintype "passive"))
      (node (ref "R75") (pin "2") (pinfunction "2_2") (pintype "passive"))
    )
    (net (code "44") (name "Net-(D4-C)") (class "Default")
      (node (ref "D4") (pin "1") (pinfunction "C_1") (pintype "passive"))
      (node (ref "K2") (pin "A2") (pinfunction "2_A2") (pintype "passive"))
      (node (ref "Q6") (pin "2") (pinfunction "DRAIN_2") (pintype "passive"))
      (node (ref "Q6") (pin "4") (pinfunction "DRAIN_4") (pintype "passive"))
      (node (ref "R79") (pin "2") (pinfunction "2_2") (pintype "passive"))
    )
    (net (code "45") (name "Net-(D5-A)") (class "Default")
      (node (ref "D5") (pin "1") (pinfunction "A_1") (pintype "passive"))
      (node (ref "Q6") (pin "1") (pinfunction "GATE_1") (pintype "passive"))
      (node (ref "R76") (pin "2") (pinfunction "2_2") (pintype "passive"))
      (node (ref "R83") (pin "1") (pinfunction "1_1") (pintype "passive"))
    )
    (net (code "46") (name "Net-(D7-A)") (class "Default")
      (node (ref "D7") (pin "1") (pinfunction "A_1") (pintype "passive"))
      (node (ref "Q8") (pin "1") (pinfunction "GATE_1") (pintype "passive"))
      (node (ref "R86") (pin "1") (pinfunction "1_1") (pintype "passive"))
      (node (ref "R87") (pin "2") (pinfunction "2_2") (pintype "passive"))
    )
    (net (code "47") (name "Net-(D14-A)") (class "Default")
      (node (ref "D14") (pin "1") (pinfunction "A_1") (pintype "passive"))
      (node (ref "Q2") (pin "1") (pinfunction "GATE_1") (pintype "passive"))
      (node (ref "R26") (pin "1") (pinfunction "1_1") (pintype "passive"))
      (node (ref "R27") (pin "2") (pinfunction "2_2") (pintype "passive"))
    )
    (net (code "48") (name "Net-(IC1-PA2)") (class "Default")
      (node (ref "IC1") (pin "19") (pinfunction "PA2_19") (pintype "bidirectional"))
      (node (ref "R91") (pin "2") (pinfunction "2_2") (pintype "passive"))
    )
    (net (code "49") (name "Net-(IC1-PF0-OSC_IN)") (class "Default")
      (node (ref "C1") (pin "2") (pinfunction "2_2") (pintype "passive"))
      (node (ref "IC1") (pin "10") (pinfunction "PF0-OSC_IN_10") (pintype "bidirectional"))
      (node (ref "IC2") (pin "1") (pinfunction "INPUT_1") (pintype "passive"))
      (node (ref "R2") (pin "2") (pinfunction "2_2") (pintype "passive"))
    )
    (net (code "50") (name "Net-(IC1-PF1-OSC_OUT)") (class "Default")
      (node (ref "C2") (pin "2") (pinfunction "2_2") (pintype "passive"))
      (node (ref "IC1") (pin "11") (pinfunction "PF1-OSC_OUT_11") (pintype "bidirectional"))
      (node (ref "IC2") (pin "3") (pinfunction "OUTPUT_3") (pintype "passive"))
      (node (ref "R2") (pin "1") (pinfunction "1_1") (pintype "passive"))
    )
    (net (code "51") (name "Net-(IC4-IN-)") (class "Default")
      (node (ref "IC4") (pin "4") (pinfunction "IN-_4") (pintype "passive"))
      (node (ref "R33") (pin "2") (pinfunction "2_2") (pintype "passive"))
    )
    (net (code "52") (name "Net-(IC5-IN+)") (class "Default")
      (node (ref "IC5") (pin "3") (pinfunction "IN+_3") (pintype "passive"))
      (node (ref "R102") (pin "1") (pinfunction "1_1") (pintype "passive"))
      (node (ref "R36") (pin "1") (pinfunction "1_1") (pintype "passive"))
    )
    (net (code "53") (name "Net-(IC5-IN-)") (class "Default")
      (node (ref "IC5") (pin "4") (pinfunction "IN-_4") (pintype "passive"))
      (node (ref "R35") (pin "1") (pinfunction "1_1") (pintype "passive"))
      (node (ref "R37") (pin "2") (pinfunction "2_2") (pintype "passive"))
    )
    (net (code "54") (name "Net-(IC5-OUT)") (class "Default")
      (node (ref "IC5") (pin "1") (pinfunction "OUT_1") (pintype "passive"))
      (node (ref "R37") (pin "1") (pinfunction "1_1") (pintype "passive"))
      (node (ref "R38") (pin "2") (pinfunction "2_2") (pintype "passive"))
      (node (ref "R40") (pin "1") (pinfunction "1_1") (pintype "passive"))
    )
    (net (code "55") (name "Net-(IC6-IN+)") (class "Default")
      (node (ref "IC6") (pin "3") (pinfunction "IN+_3") (pintype "passive"))
      (node (ref "R41") (pin "2") (pinfunction "2_2") (pintype "passive"))
    )
    (net (code "56") (name "Net-(IC6-IN-)") (class "Default")
      (node (ref "IC6") (pin "4") (pinfunction "IN-_4") (pintype "passive"))
      (node (ref "R43") (pin "2") (pinfunction "2_2") (pintype "passive"))
    )
    (net (code "57") (name "Net-(IC6-OUT)") (class "Default")
      (node (ref "IC6") (pin "1") (pinfunction "OUT_1") (pintype "passive"))
      (node (ref "R44") (pin "2") (pinfunction "2_2") (pintype "passive"))
    )
    (net (code "58") (name "Net-(IC7-IN-)") (class "Default")
      (node (ref "IC7") (pin "4") (pinfunction "IN-_4") (pintype "passive"))
      (node (ref "R47") (pin "2") (pinfunction "2_2") (pintype "passive"))
    )
    (net (code "59") (name "Net-(IC8-IN+)") (class "Default")
      (node (ref "IC8") (pin "3") (pinfunction "IN+_3") (pintype "passive"))
      (node (ref "R101") (pin "1") (pinfunction "1_1") (pintype "passive"))
      (node (ref "R50") (pin "1") (pinfunction "1_1") (pintype "passive"))
    )
    (net (code "60") (name "Net-(IC8-IN-)") (class "Default")
      (node (ref "IC8") (pin "4") (pinfunction "IN-_4") (pintype "passive"))
      (node (ref "R49") (pin "1") (pinfunction "1_1") (pintype "passive"))
      (node (ref "R51") (pin "2") (pinfunction "2_2") (pintype "passive"))
    )
    (net (code "61") (name "Net-(IC8-OUT)") (class "Default")
      (node (ref "IC8") (pin "1") (pinfunction "OUT_1") (pintype "passive"))
      (node (ref "R51") (pin "1") (pinfunction "1_1") (pintype "passive"))
      (node (ref "R52") (pin "2") (pinfunction "2_2") (pintype "passive"))
      (node (ref "R54") (pin "1") (pinfunction "1_1") (pintype "passive"))
    )
    (net (code "62") (name "Net-(IC9-IN+)") (class "Default")
      (node (ref "IC9") (pin "3") (pinfunction "IN+_3") (pintype "passive"))
      (node (ref "R57") (pin "2") (pinfunction "2_2") (pintype "passive"))
    )
    (net (code "63") (name "Net-(IC9-IN-)") (class "Default")
      (node (ref "IC9") (pin "4") (pinfunction "IN-_4") (pintype "passive"))
      (node (ref "R56") (pin "2") (pinfunction "2_2") (pintype "passive"))
    )
    (net (code "64") (name "Net-(IC9-OUT)") (class "Default")
      (node (ref "IC9") (pin "1") (pinfunction "OUT_1") (pintype "passive"))
      (node (ref "R58") (pin "2") (pinfunction "2_2") (pintype "passive"))
    )
    (net (code "65") (name "Net-(IC10-D)") (class "Default")
      (node (ref "IC10") (pin "4") (pinfunction "D_4") (pintype "bidirectional"))
      (node (ref "R98") (pin "1") (pinfunction "1_1") (pintype "passive"))
    )
    (net (code "66") (name "Net-(IC10-DE)") (class "Default")
      (node (ref "IC10") (pin "3") (pinfunction "DE_3") (pintype "bidirectional"))
      (node (ref "R96") (pin "2") (pinfunction "2_2") (pintype "passive"))
      (node (ref "R97") (pin "1") (pinfunction "1_1") (pintype "passive"))
    )
    (net (code "67") (name "Net-(IC10-R)") (class "Default")
      (node (ref "IC10") (pin "1") (pinfunction "R_1") (pintype "bidirectional"))
      (node (ref "R93") (pin "2") (pinfunction "2_2") (pintype "passive"))
    )
    (net (code "68") (name "Net-(IC10-{slash}RE)") (class "Default")
      (node (ref "IC10") (pin "2") (pinfunction "/RE_2") (pintype "bidirectional"))
      (node (ref "R96") (pin "1") (pinfunction "1_1") (pintype "passive"))
    )
    (net (code "69") (name "Net-(J1-ID)") (class "Default")
      (node (ref "J1") (pin "4") (pinfunction "ID_4") (pintype "bidirectional"))
      (node (ref "R1") (pin "1") (pinfunction "1_1") (pintype "passive"))
    )
    (net (code "70") (name "Net-(J4-Pad02)") (class "Default")
      (node (ref "J4") (pin "02") (pinfunction "02_02") (pintype "passive"))
      (node (ref "R20") (pin "2") (pinfunction "2_2") (pintype "passive"))
    )
    (net (code "71") (name "Net-(J4-Pad03)") (class "Default")
      (node (ref "J4") (pin "03") (pinfunction "03_03") (pintype "passive"))
      (node (ref "R21") (pin "2") (pinfunction "2_2") (pintype "passive"))
    )
    (net (code "72") (name "Net-(Q1-B)") (class "Default")
      (node (ref "Q1") (pin "1") (pinfunction "B_1") (pintype "passive"))
      (node (ref "R3") (pin "1") (pinfunction "1_1") (pintype "passive"))
      (node (ref "R4") (pin "1") (pinfunction "1_1") (pintype "passive"))
    )
    (net (code "73") (name "Net-(Q3-D)") (class "Default")
      (node (ref "Q3") (pin "3") (pinfunction "D_3") (pintype "passive"))
      (node (ref "R27") (pin "1") (pinfunction "1_1") (pintype "passive"))
    )
    (net (code "74") (name "Net-(Q3-G)") (class "Default")
      (node (ref "Q3") (pin "1") (pinfunction "G_1") (pintype "passive"))
      (node (ref "R28") (pin "2") (pinfunction "2_2") (pintype "passive"))
      (node (ref "R29") (pin "1") (pinfunction "1_1") (pintype "passive"))
    )
    (net (code "75") (name "Net-(Q5-D)") (class "Default")
      (node (ref "Q5") (pin "3") (pinfunction "D_3") (pintype "passive"))
      (node (ref "R75") (pin "1") (pinfunction "1_1") (pintype "passive"))
    )
    (net (code "76") (name "Net-(Q5-G)") (class "Default")
      (node (ref "Q5") (pin "1") (pinfunction "G_1") (pintype "passive"))
      (node (ref "R71") (pin "2") (pinfunction "2_2") (pintype "passive"))
      (node (ref "R74") (pin "1") (pinfunction "1_1") (pintype "passive"))
    )
    (net (code "77") (name "Net-(Q7-D)") (class "Default")
      (node (ref "Q7") (pin "3") (pinfunction "D_3") (pintype "passive"))
      (node (ref "R76") (pin "1") (pinfunction "1_1") (pintype "passive"))
    )
    (net (code "78") (name "Net-(Q7-G)") (class "Default")
      (node (ref "Q7") (pin "1") (pinfunction "G_1") (pintype "passive"))
      (node (ref "R77") (pin "1") (pinfunction "1_1") (pintype "passive"))
      (node (ref "R78") (pin "2") (pinfunction "2_2") (pintype "passive"))
    )
    (net (code "79") (name "Net-(Q9-D)") (class "Default")
      (node (ref "Q9") (pin "3") (pinfunction "D_3") (pintype "passive"))
      (node (ref "R87") (pin "1") (pinfunction "1_1") (pintype "passive"))
    )
    (net (code "80") (name "Net-(Q9-G)") (class "Default")
      (node (ref "Q9") (pin "1") (pinfunction "G_1") (pintype "passive"))
      (node (ref "R85") (pin "1") (pinfunction "1_1") (pintype "passive"))
      (node (ref "R88") (pin "2") (pinfunction "2_2") (pintype "passive"))
    )
    (net (code "81") (name "Net-(R10-Pad1)") (class "Default")
      (node (ref "R10") (pin "1") (pinfunction "1_1") (pintype "passive"))
      (node (ref "R11") (pin "1") (pinfunction "1_1") (pintype "passive"))
    )
    (net (code "82") (name "Net-(R13-Pad2)") (class "Default")
      (node (ref "R13") (pin "2") (pinfunction "2_2") (pintype "passive"))
      (node (ref "R14") (pin "1") (pinfunction "1_1") (pintype "passive"))
      (node (ref "R7") (pin "2") (pinfunction "2_2") (pintype "passive"))
      (node (ref "R8") (pin "2") (pinfunction "2_2") (pintype "passive"))
    )
    (net (code "83") (name "Net-(R14-Pad2)") (class "Default")
      (node (ref "R14") (pin "2") (pinfunction "2_2") (pintype "passive"))
      (node (ref "R15") (pin "2") (pinfunction "2_2") (pintype "passive"))
    )
    (net (code "84") (name "Net-(R16-Pad1)") (class "Default")
      (node (ref "R16") (pin "1") (pinfunction "1_1") (pintype "passive"))
      (node (ref "X3") (pin "6") (pinfunction "6_6") (pintype "bidirectional"))
    )
    (net (code "85") (name "Net-(R17-Pad1)") (class "Default")
      (node (ref "R17") (pin "1") (pinfunction "1_1") (pintype "passive"))
      (node (ref "X3") (pin "8") (pinfunction "8_8") (pintype "bidirectional"))
    )
    (net (code "86") (name "Net-(R18-Pad1)") (class "Default")
      (node (ref "R18") (pin "1") (pinfunction "1_1") (pintype "passive"))
      (node (ref "X3") (pin "10") (pinfunction "10_10") (pintype "bidirectional"))
    )
    (net (code "87") (name "Net-(R22-Pad2)") (class "Default")
      (node (ref "R22") (pin "2") (pinfunction "2_2") (pintype "passive"))
      (node (ref "R25") (pin "1") (pinfunction "1_1") (pintype "passive"))
      (node (ref "V4") (pin "1") (pinfunction "1_1") (pintype "passive"))
      (node (ref "X6") (pin "1") (pinfunction "1_1") (pintype "bidirectional"))
    )
    (net (code "88") (name "Net-(R61-Pad2)") (class "Default")
      (node (ref "R61") (pin "2") (pinfunction "2_2") (pintype "passive"))
      (node (ref "X8") (pin "6") (pinfunction "6_6") (pintype "passive"))
    )
    (net (code "89") (name "Net-(R62-Pad2)") (class "Default")
      (node (ref "R62") (pin "2") (pinfunction "2_2") (pintype "passive"))
      (node (ref "X8") (pin "1") (pinfunction "1_1") (pintype "passive"))
    )
    (net (code "90") (name "Net-(R63-Pad2)") (class "Default")
      (node (ref "R63") (pin "2") (pinfunction "2_2") (pintype "passive"))
      (node (ref "X8") (pin "2") (pinfunction "2_2") (pintype "passive"))
    )
    (net (code "91") (name "Net-(R65-Pad1)") (class "Default")
      (node (ref "R65") (pin "1") (pinfunction "1_1") (pintype "passive"))
      (node (ref "X8") (pin "5") (pinfunction "5_5") (pintype "passive"))
    )
    (net (code "92") (name "Net-(R66-Pad2)") (class "Default")
      (node (ref "R66") (pin "2") (pinfunction "2_2") (pintype "passive"))
      (node (ref "X9") (pin "6") (pinfunction "6_6") (pintype "passive"))
    )
    (net (code "93") (name "Net-(R67-Pad2)") (class "Default")
      (node (ref "R67") (pin "2") (pinfunction "2_2") (pintype "passive"))
      (node (ref "X9") (pin "1") (pinfunction "1_1") (pintype "passive"))
    )
    (net (code "94") (name "Net-(R68-Pad2)") (class "Default")
      (node (ref "R68") (pin "2") (pinfunction "2_2") (pintype "passive"))
      (node (ref "X9") (pin "2") (pinfunction "2_2") (pintype "passive"))
    )
    (net (code "95") (name "Net-(R70-Pad1)") (class "Default")
      (node (ref "R70") (pin "1") (pinfunction "1_1") (pintype "passive"))
      (node (ref "X9") (pin "5") (pinfunction "5_5") (pintype "passive"))
    )
    (net (code "96") (name "Net-(R80-Pad1)") (class "Default")
      (node (ref "R80") (pin "1") (pinfunction "1_1") (pintype "passive"))
      (node (ref "R84") (pin "2") (pinfunction "2_2") (pintype "passive"))
      (node (ref "V8") (pin "1") (pinfunction "1_1") (pintype "passive"))
      (node (ref "X4") (pin "1") (pinfunction "1_1") (pintype "bidirectional"))
    )
    (net (code "97") (name "Net-(R81-Pad1)") (class "Default")
      (node (ref "R81") (pin "1") (pinfunction "1_1") (pintype "passive"))
      (node (ref "R82") (pin "2") (pinfunction "2_2") (pintype "passive"))
    )
    (net (code "98") (name "Net-(R93-Pad1)") (class "Default")
      (node (ref "R93") (pin "1") (pinfunction "1_1") (pintype "passive"))
      (node (ref "R94") (pin "2") (pinfunction "2_2") (pintype "passive"))
      (node (ref "R95") (pin "1") (pinfunction "1_1") (pintype "passive"))
    )
    (net (code "99") (name "O2_SENSOR1_C") (class "Default")
      (node (ref "C11") (pin "1") (pinfunction "1_1") (pintype "passive"))
      (node (ref "IC4") (pin "1") (pinfunction "OUT_1") (pintype "passive"))
      (node (ref "X17") (pin "2") (pinfunction "2_2") (pintype "bidirectional"))
    )
    (net (code "100") (name "O2_SENSOR1_R") (class "Default")
      (node (ref "R34") (pin "1") (pinfunction "1_1") (pintype "passive"))
      (node (ref "X17") (pin "1") (pinfunction "1_1") (pintype "bidirectional"))
    )
    (net (code "101") (name "O2_SENSOR1_S") (class "Default")
      (node (ref "R35") (pin "2") (pinfunction "2_2") (pintype "passive"))
      (node (ref "X17") (pin "3") (pinfunction "3_3") (pintype "bidirectional"))
    )
    (net (code "102") (name "O2_SENSOR2_C") (class "Default")
      (node (ref "C17") (pin "1") (pinfunction "1_1") (pintype "passive"))
      (node (ref "IC7") (pin "1") (pinfunction "OUT_1") (pintype "passive"))
      (node (ref "X18") (pin "2") (pinfunction "2_2") (pintype "bidirectional"))
    )
    (net (code "103") (name "O2_SENSOR2_R") (class "Default")
      (node (ref "R48") (pin "1") (pinfunction "1_1") (pintype "passive"))
      (node (ref "X18") (pin "1") (pinfunction "1_1") (pintype "bidirectional"))
    )
    (net (code "104") (name "O2_SENSOR2_S") (class "Default")
      (node (ref "R49") (pin "2") (pinfunction "2_2") (pintype "passive"))
      (node (ref "X18") (pin "3") (pinfunction "3_3") (pintype "bidirectional"))
    )
    (net (code "105") (name "RS485-A") (class "Default")
      (node (ref "IC10") (pin "6") (pinfunction "A_6") (pintype "bidirectional"))
      (node (ref "J3") (pin "1") (pinfunction "1_1") (pintype "passive"))
      (node (ref "R100") (pin "2") (pinfunction "2_2") (pintype "passive"))
      (node (ref "V9") (pin "2") (pinfunction "2_2") (pintype "passive"))
    )
    (net (code "106") (name "RS485-B") (class "Default")
      (node (ref "IC10") (pin "7") (pinfunction "B_7") (pintype "bidirectional"))
      (node (ref "J3") (pin "2") (pinfunction "2_2") (pintype "passive"))
      (node (ref "R99") (pin "2") (pinfunction "2_2") (pintype "passive"))
      (node (ref "V10") (pin "2") (pinfunction "2_2") (pintype "passive"))
    )
    (net (code "107") (name "TEMP_SENSOR_A") (class "Default")
      (node (ref "R92") (pin "2") (pinfunction "2_2") (pintype "passive"))
      (node (ref "X24") (pin "1") (pinfunction "1_1") (pintype "bidirectional"))
    )
    (net (code "108") (name "TEMP_SENSOR_C") (class "Default")
      (node (ref "R90") (pin "1") (pinfunction "1_1") (pintype "passive"))
      (node (ref "R91") (pin "1") (pinfunction "1_1") (pintype "passive"))
      (node (ref "X24") (pin "3") (pinfunction "3_3") (pintype "bidirectional"))
    )
    (net (code "109") (name "USB_DM") (class "Default")
      (node (ref "IC1") (pin "43") (pinfunction "PA11_[PA9]_43") (pintype "bidirectional"))
      (node (ref "J1") (pin "2") (pinfunction "D-_2") (pintype "bidirectional"))
      (node (ref "V2") (pin "2") (pinfunction "2_2") (pintype "passive"))
    )
    (net (code "110") (name "USB_DP") (class "Default")
      (node (ref "IC1") (pin "44") (pinfunction "PA12_[PA10]_44") (pintype "bidirectional"))
      (node (ref "J1") (pin "3") (pinfunction "D+_3") (pintype "bidirectional"))
      (node (ref "V1") (pin "2") (pinfunction "2_2") (pintype "passive"))
    )
    (net (code "111") (name "V-5V0") (class "Default")
      (node (ref "C31") (pin "1") (pinfunction "1_1") (pintype "passive"))
      (node (ref "X10") (pin "6") (pinfunction "6_6") (pintype "passive"))
    )
    (net (code "112") (name "V3V3") (class "Default")
      (node (ref "C3") (pin "1") (pinfunction "1_1") (pintype "passive"))
      (node (ref "C30") (pin "1") (pinfunction "1_1") (pintype "passive"))
      (node (ref "C34") (pin "1") (pinfunction "+_1") (pintype "passive"))
      (node (ref "C37") (pin "1") (pinfunction "1_1") (pintype "passive"))
      (node (ref "C4") (pin "2") (pinfunction "2_2") (pintype "passive"))
      (node (ref "C6") (pin "1") (pinfunction "1_1") (pintype "passive"))
      (node (ref "C7") (pin "1") (pinfunction "1_1") (pintype "passive"))
      (node (ref "C8") (pin "1") (pinfunction "1_1") (pintype "passive"))
      (node (ref "C9") (pin "1") (pinfunction "1_1") (pintype "passive"))
      (node (ref "IC1") (pin "7") (pinfunction "VREF+_7") (pintype "bidirectional"))
      (node (ref "IC1") (pin "8") (pinfunction "VDD/VDDA_8") (pintype "bidirectional"))
      (node (ref "J4") (pin "01") (pinfunction "01_01") (pintype "passive"))
      (node (ref "R10") (pin "2") (pinfunction "2_2") (pintype "passive"))
      (node (ref "R19") (pin "2") (pinfunction "2_2") (pintype "passive"))
      (node (ref "R23") (pin "2") (pinfunction "2_2") (pintype "passive"))
      (node (ref "R24") (pin "2") (pinfunction "2_2") (pintype "passive"))
      (node (ref "R25") (pin "2") (pinfunction "2_2") (pintype "passive"))
      (node (ref "R59") (pin "2") (pinfunction "2_2") (pintype "passive"))
      (node (ref "R60") (pin "2") (pinfunction "2_2") (pintype "passive"))
      (node (ref "R80") (pin "2") (pinfunction "2_2") (pintype "passive"))
      (node (ref "R90") (pin "2") (pinfunction "2_2") (pintype "passive"))
      (node (ref "X10") (pin "4") (pinfunction "4_4") (pintype "passive"))
      (node (ref "X3") (pin "2") (pinfunction "2_2") (pintype "bidirectional"))
    )
    (net (code "113") (name "V5V0") (class "Default")
      (node (ref "C10") (pin "1") (pinfunction "1_1") (pintype "passive"))
      (node (ref "C12") (pin "1") (pinfunction "1_1") (pintype "passive"))
      (node (ref "C15") (pin "1") (pinfunction "1_1") (pintype "passive"))
      (node (ref "C16") (pin "1") (pinfunction "1_1") (pintype "passive"))
      (node (ref "C18") (pin "1") (pinfunction "1_1") (pintype "passive"))
      (node (ref "C21") (pin "1") (pinfunction "1_1") (pintype "passive"))
      (node (ref "C24") (pin "2") (pinfunction "2_2") (pintype "passive"))
      (node (ref "C25") (pin "2") (pinfunction "2_2") (pintype "passive"))
      (node (ref "C29") (pin "1") (pinfunction "1_1") (pintype "passive"))
      (node (ref "C33") (pin "1") (pinfunction "+_1") (pintype "passive"))
      (node (ref "C36") (pin "1") (pinfunction "1_1") (pintype "passive"))
      (node (ref "IC10") (pin "8") (pinfunction "VCC_8") (pintype "bidirectional"))
      (node (ref "IC4") (pin "5") (pinfunction "VCC_5") (pintype "passive"))
      (node (ref "IC5") (pin "5") (pinfunction "VCC_5") (pintype "passive"))
      (node (ref "IC6") (pin "5") (pinfunction "VCC_5") (pintype "passive"))
      (node (ref "IC7") (pin "5") (pinfunction "VCC_5") (pintype "passive"))
      (node (ref "IC8") (pin "5") (pinfunction "VCC_5") (pintype "passive"))
      (node (ref "IC9") (pin "5") (pinfunction "VCC_5") (pintype "passive"))
      (node (ref "J2") (pin "04") (pinfunction "04_04") (pintype "passive"))
      (node (ref "R32") (pin "2") (pinfunction "2_2") (pintype "passive"))
      (node (ref "R46") (pin "2") (pinfunction "2_2") (pintype "passive"))
      (node (ref "R6") (pin "1") (pinfunction "1_1") (pintype "passive"))
      (node (ref "R64") (pin "1") (pinfunction "1_1") (pintype "passive"))
      (node (ref "R69") (pin "1") (pinfunction "1_1") (pintype "passive"))
      (node (ref "R9") (pin "2") (pinfunction "2_2") (pintype "passive"))
      (node (ref "X10") (pin "2") (pinfunction "2_2") (pintype "passive"))
      (node (ref "X8") (pin "3") (pinfunction "3_3") (pintype "passive"))
      (node (ref "X9") (pin "3") (pinfunction "3_3") (pintype "passive"))
    )
    (net (code "114") (name "V24V0") (class "Default")
      (node (ref "C27") (pin "1") (pinfunction "1_1") (pintype "passive"))
      (node (ref "X10") (pin "3") (pinfunction "3_3") (pintype "passive"))
    )
    (net (code "115") (name "VBUS") (class "Default")
      (node (ref "J1") (pin "1") (pinfunction "VBUS_1") (pintype "power_in"))
    )
    (net (code "116") (name "VREF_O2") (class "Default")
      (node (ref "IC4") (pin "3") (pinfunction "IN+_3") (pintype "passive"))
      (node (ref "IC7") (pin "3") (pinfunction "IN+_3") (pintype "passive"))
      (node (ref "R31") (pin "2") (pinfunction "2_2") (pintype "passive"))
      (node (ref "R32") (pin "1") (pinfunction "1_1") (pintype "passive"))
      (node (ref "R36") (pin "2") (pinfunction "2_2") (pintype "passive"))
      (node (ref "R42") (pin "1") (pinfunction "1_1") (pintype "passive"))
      (node (ref "R45") (pin "2") (pinfunction "2_2") (pintype "passive"))
      (node (ref "R46") (pin "1") (pinfunction "1_1") (pintype "passive"))
      (node (ref "R50") (pin "2") (pinfunction "2_2") (pintype "passive"))
      (node (ref "R55") (pin "1") (pinfunction "1_1") (pintype "passive"))
    )
    (net (code "117") (name "V_12V0") (class "Default")
      (node (ref "C26") (pin "1") (pinfunction "1_1") (pintype "passive"))
      (node (ref "C32") (pin "1") (pinfunction "+_1") (pintype "passive"))
      (node (ref "D14") (pin "3") (pinfunction "C_3") (pintype "passive"))
      (node (ref "D3") (pin "3") (pinfunction "C_3") (pintype "passive"))
      (node (ref "D5") (pin "3") (pinfunction "C_3") (pintype "passive"))
      (node (ref "D7") (pin "3") (pinfunction "C_3") (pintype "passive"))
      (node (ref "Q2") (pin "3") (pinfunction "SOURCE_3") (pintype "passive"))
      (node (ref "Q4") (pin "3") (pinfunction "SOURCE_3") (pintype "passive"))
      (node (ref "Q6") (pin "3") (pinfunction "SOURCE_3") (pintype "passive"))
      (node (ref "Q8") (pin "3") (pinfunction "SOURCE_3") (pintype "passive"))
      (node (ref "R26") (pin "2") (pinfunction "2_2") (pintype "passive"))
      (node (ref "R73") (pin "2") (pinfunction "2_2") (pintype "passive"))
      (node (ref "R83") (pin "2") (pinfunction "2_2") (pintype "passive"))
      (node (ref "R86") (pin "2") (pinfunction "2_2") (pintype "passive"))
      (node (ref "X10") (pin "1") (pinfunction "1_1") (pintype "passive"))
    )
    (net (code "118") (name "unconnected-(FID1-PadP$1)") (class "Default")
      (node (ref "FID1") (pin "P$1") (pinfunction "P$1_P$1") (pintype "bidirectional"))
    )
    (net (code "119") (name "unconnected-(FID2-PadP$1)") (class "Default")
      (node (ref "FID2") (pin "P$1") (pinfunction "P$1_P$1") (pintype "bidirectional"))
    )
    (net (code "120") (name "unconnected-(IC1-PA3-Pad20)") (class "Default")
      (node (ref "IC1") (pin "20") (pinfunction "PA3_20") (pintype "bidirectional"))
    )
    (net (code "121") (name "unconnected-(IC1-PA4-Pad21)") (class "Default")
      (node (ref "IC1") (pin "21") (pinfunction "PA4_21") (pintype "bidirectional"))
    )
    (net (code "122") (name "unconnected-(IC1-PA5-Pad22)") (class "Default")
      (node (ref "IC1") (pin "22") (pinfunction "PA5_22") (pintype "bidirectional"))
    )
    (net (code "123") (name "unconnected-(IC1-PA10-Pad42)") (class "Default")
      (node (ref "IC1") (pin "42") (pinfunction "PA10_42") (pintype "bidirectional"))
    )
    (net (code "124") (name "unconnected-(IC1-PB1-Pad28)") (class "Default")
      (node (ref "IC1") (pin "28") (pinfunction "PB1_28") (pintype "bidirectional"))
    )
    (net (code "125") (name "unconnected-(IC1-PB2-Pad29)") (class "Default")
      (node (ref "IC1") (pin "29") (pinfunction "PB2_29") (pintype "bidirectional"))
    )
    (net (code "126") (name "unconnected-(IC1-PB3-Pad57)") (class "Default")
      (node (ref "IC1") (pin "57") (pinfunction "PB3_57") (pintype "bidirectional"))
    )
    (net (code "127") (name "unconnected-(IC1-PB4-Pad58)") (class "Default")
      (node (ref "IC1") (pin "58") (pinfunction "PB4_58") (pintype "bidirectional"))
    )
    (net (code "128") (name "unconnected-(IC1-PB5-Pad59)") (class "Default")
      (node (ref "IC1") (pin "59") (pinfunction "PB5_59") (pintype "bidirectional"))
    )
    (net (code "129") (name "unconnected-(IC1-PB6-Pad60)") (class "Default")
      (node (ref "IC1") (pin "60") (pinfunction "PB6_60") (pintype "bidirectional"))
    )
    (net (code "130") (name "unconnected-(IC1-PB7-Pad61)") (class "Default")
      (node (ref "IC1") (pin "61") (pinfunction "PB7_61") (pintype "bidirectional"))
    )
    (net (code "131") (name "unconnected-(IC1-PB8-Pad62)") (class "Default")
      (node (ref "IC1") (pin "62") (pinfunction "PB8_62") (pintype "bidirectional"))
    )
    (net (code "132") (name "unconnected-(IC1-PB9-Pad63)") (class "Default")
      (node (ref "IC1") (pin "63") (pinfunction "PB9_63") (pintype "bidirectional"))
    )
    (net (code "133") (name "unconnected-(IC1-PB10-Pad30)") (class "Default")
      (node (ref "IC1") (pin "30") (pinfunction "PB10_30") (pintype "bidirectional"))
    )
    (net (code "134") (name "unconnected-(IC1-PB11-Pad31)") (class "Default")
      (node (ref "IC1") (pin "31") (pinfunction "PB11_31") (pintype "bidirectional"))
    )
    (net (code "135") (name "unconnected-(IC1-PB12-Pad32)") (class "Default")
      (node (ref "IC1") (pin "32") (pinfunction "PB12_32") (pintype "bidirectional"))
    )
    (net (code "136") (name "unconnected-(IC1-PB13-Pad33)") (class "Default")
      (node (ref "IC1") (pin "33") (pinfunction "PB13_33") (pintype "bidirectional"))
    )
    (net (code "137") (name "unconnected-(IC1-PB14-Pad34)") (class "Default")
      (node (ref "IC1") (pin "34") (pinfunction "PB14_34") (pintype "bidirectional"))
    )
    (net (code "138") (name "unconnected-(IC1-PB15-Pad35)") (class "Default")
      (node (ref "IC1") (pin "35") (pinfunction "PB15_35") (pintype "bidirectional"))
    )
    (net (code "139") (name "unconnected-(IC1-PC2-Pad15)") (class "Default")
      (node (ref "IC1") (pin "15") (pinfunction "PC2_15") (pintype "bidirectional"))
    )
    (net (code "140") (name "unconnected-(IC1-PC3-Pad16)") (class "Default")
      (node (ref "IC1") (pin "16") (pinfunction "PC3_16") (pintype "bidirectional"))
    )
    (net (code "141") (name "unconnected-(IC1-PC4-Pad25)") (class "Default")
      (node (ref "IC1") (pin "25") (pinfunction "PC4_25") (pintype "bidirectional"))
    )
    (net (code "142") (name "unconnected-(IC1-PC6-Pad38)") (class "Default")
      (node (ref "IC1") (pin "38") (pinfunction "PC6_38") (pintype "bidirectional"))
    )
    (net (code "143") (name "unconnected-(IC1-PC7-Pad39)") (class "Default")
      (node (ref "IC1") (pin "39") (pinfunction "PC7_39") (pintype "bidirectional"))
    )
    (net (code "144") (name "unconnected-(IC1-PC9-Pad49)") (class "Default")
      (node (ref "IC1") (pin "49") (pinfunction "PC9_49") (pintype "bidirectional"))
    )
    (net (code "145") (name "unconnected-(IC1-PC14-OSC32_IN-Pad4)") (class "Default")
      (node (ref "IC1") (pin "4") (pinfunction "PC14-OSC32_IN_4") (pintype "bidirectional"))
    )
    (net (code "146") (name "unconnected-(IC1-PC15-OSC32_OUT-Pad5)") (class "Default")
      (node (ref "IC1") (pin "5") (pinfunction "PC15-OSC32_OUT_5") (pintype "bidirectional"))
    )
    (net (code "147") (name "unconnected-(IC1-PD0-Pad50)") (class "Default")
      (node (ref "IC1") (pin "50") (pinfunction "PD0_50") (pintype "bidirectional"))
    )
    (net (code "148") (name "unconnected-(IC1-PD2-Pad52)") (class "Default")
      (node (ref "IC1") (pin "52") (pinfunction "PD2_52") (pintype "bidirectional"))
    )
    (net (code "149") (name "unconnected-(IC1-PD3-Pad53)") (class "Default")
      (node (ref "IC1") (pin "53") (pinfunction "PD3_53") (pintype "bidirectional"))
    )
    (net (code "150") (name "unconnected-(IC1-PD4-Pad54)") (class "Default")
      (node (ref "IC1") (pin "54") (pinfunction "PD4_54") (pintype "bidirectional"))
    )
    (net (code "151") (name "unconnected-(IC1-PD5-Pad55)") (class "Default")
      (node (ref "IC1") (pin "55") (pinfunction "PD5_55") (pintype "bidirectional"))
    )
    (net (code "152") (name "unconnected-(IC1-PD6-Pad56)") (class "Default")
      (node (ref "IC1") (pin "56") (pinfunction "PD6_56") (pintype "bidirectional"))
    )
    (net (code "153") (name "unconnected-(IC1-PD8-Pad40)") (class "Default")
      (node (ref "IC1") (pin "40") (pinfunction "PD8_40") (pintype "bidirectional"))
    )
    (net (code "154") (name "unconnected-(IC1-PD9-Pad41)") (class "Default")
      (node (ref "IC1") (pin "41") (pinfunction "PD9_41") (pintype "bidirectional"))
    )
    (net (code "155") (name "unconnected-(IC1-VBAT-Pad6)") (class "Default")
      (node (ref "IC1") (pin "6") (pinfunction "VBAT_6") (pintype "bidirectional"))
    )
    (net (code "156") (name "unconnected-(IC10-GND-Pad5)") (class "Default")
      (node (ref "IC10") (pin "5") (pinfunction "GND_5") (pintype "bidirectional"))
    )
    (net (code "157") (name "unconnected-(J3-Pad3)") (class "Default")
      (node (ref "J3") (pin "3") (pinfunction "3_3") (pintype "passive"))
    )
    (net (code "158") (name "unconnected-(J3-Pad4)") (class "Default")
      (node (ref "J3") (pin "4") (pinfunction "4_4") (pintype "passive"))
    )
    (net (code "159") (name "unconnected-(J3-Pad5)") (class "Default")
      (node (ref "J3") (pin "5") (pinfunction "5_5") (pintype "passive"))
    )
    (net (code "160") (name "unconnected-(J3-Pad6)") (class "Default")
      (node (ref "J3") (pin "6") (pinfunction "6_6") (pintype "passive"))
    )
    (net (code "161") (name "unconnected-(J3-Pad7)") (class "Default")
      (node (ref "J3") (pin "7") (pinfunction "7_7") (pintype "passive"))
    )
    (net (code "162") (name "unconnected-(X3-Pad1)") (class "Default")
      (node (ref "X3") (pin "1") (pinfunction "1_1") (pintype "bidirectional"))
    )
    (net (code "163") (name "unconnected-(X3-Pad3)") (class "Default")
      (node (ref "X3") (pin "3") (pinfunction "3_3") (pintype "bidirectional"))
    )
    (net (code "164") (name "unconnected-(X3-Pad5)") (class "Default")
      (node (ref "X3") (pin "5") (pinfunction "5_5") (pintype "bidirectional"))
    )
    (net (code "165") (name "unconnected-(X3-Pad7)") (class "Default")
      (node (ref "X3") (pin "7") (pinfunction "7_7") (pintype "bidirectional"))
    )
    (net (code "166") (name "unconnected-(X3-Pad9)") (class "Default")
      (node (ref "X3") (pin "9") (pinfunction "9_9") (pintype "bidirectional"))
    )
    (net (code "167") (name "unconnected-(X24-Pad2)") (class "Default")
      (node (ref "X24") (pin "2") (pinfunction "2_2") (pintype "bidirectional"))
    )
  )
)
